# EEZ_DIB_DCP405_r2B7.net
KiCad netlist of a schematic drawn in EAGLE
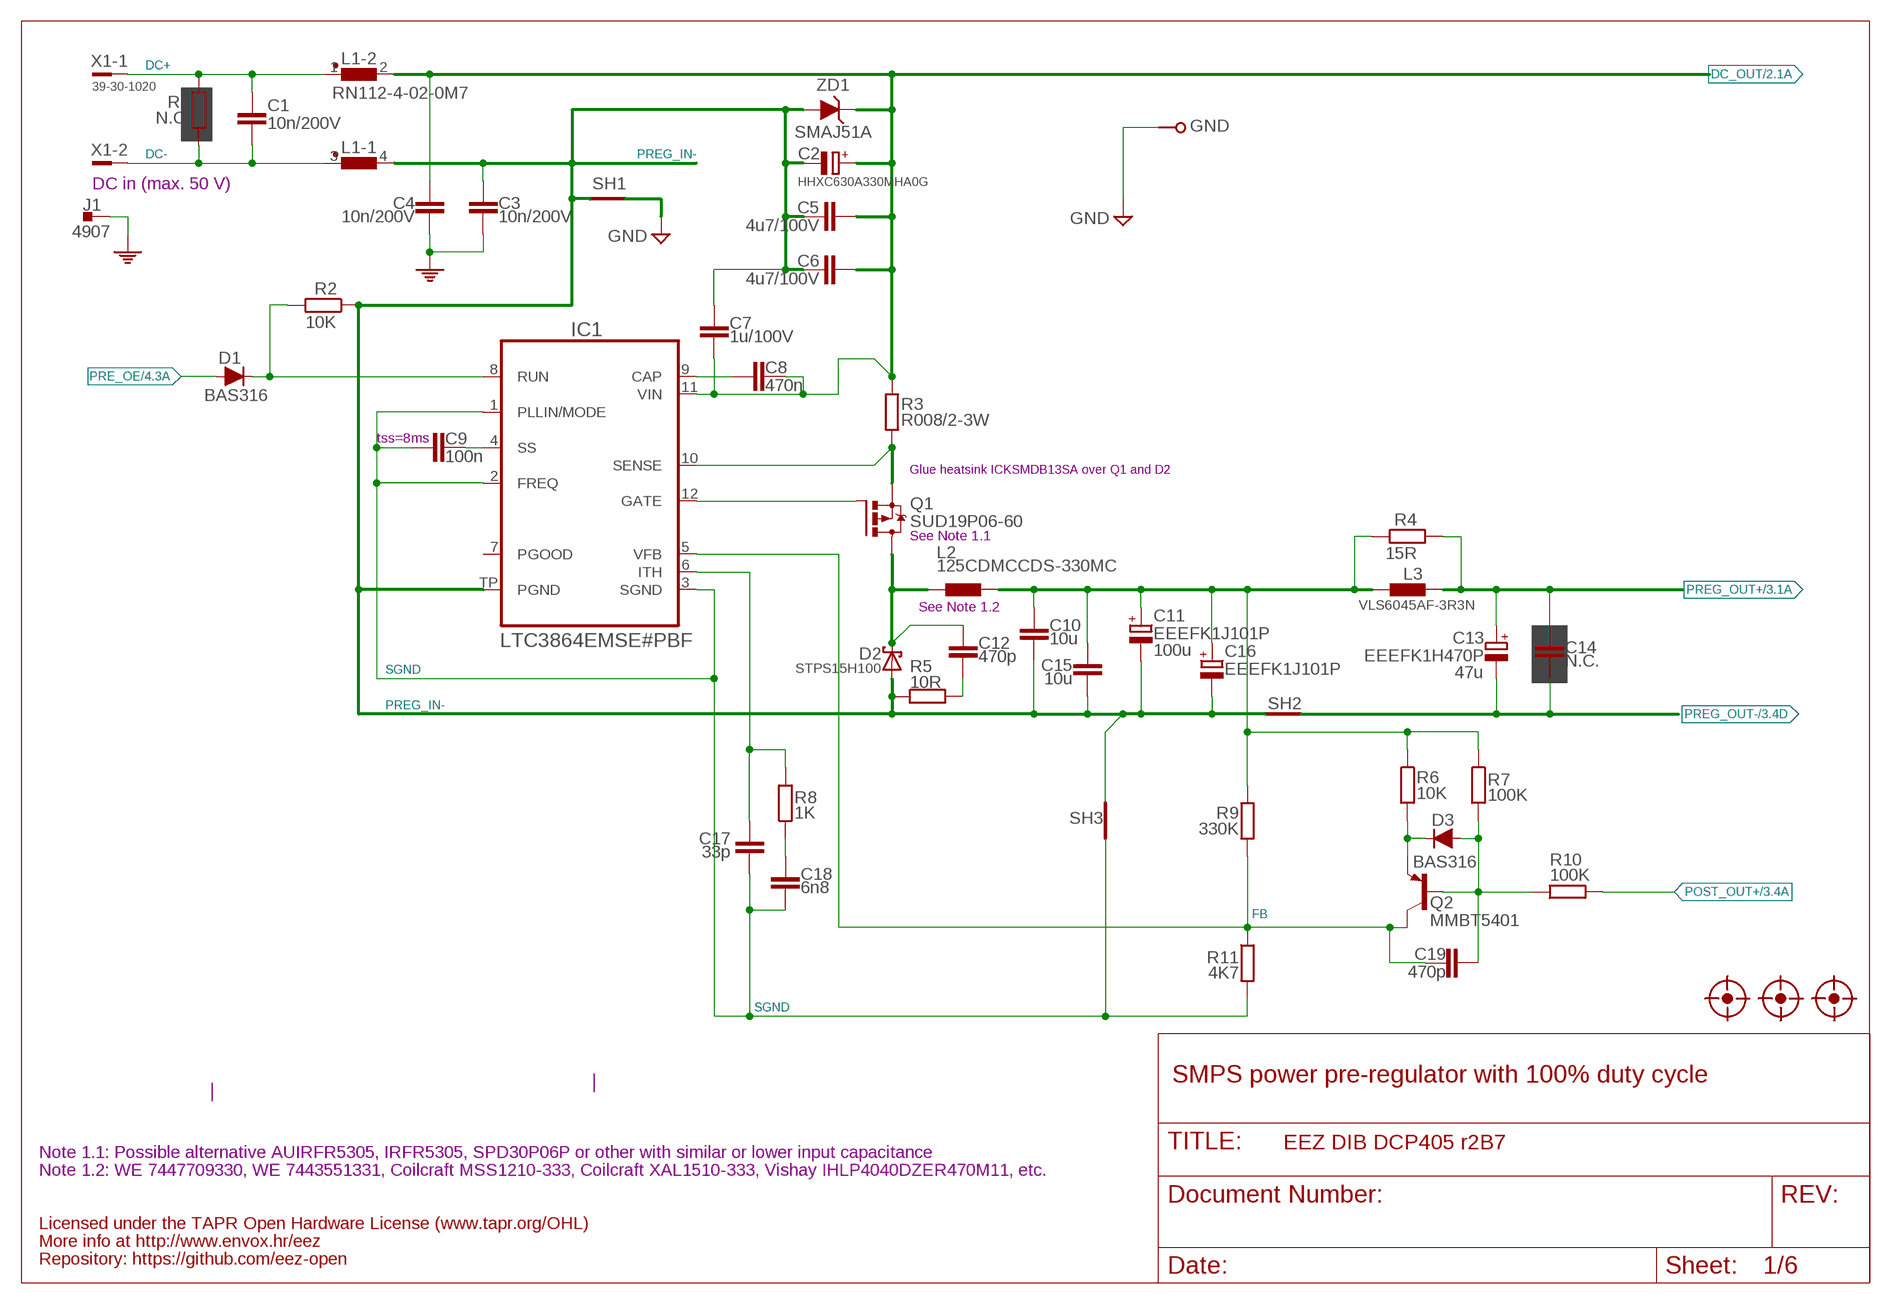
[diagram p0: schematic, sheet 1]
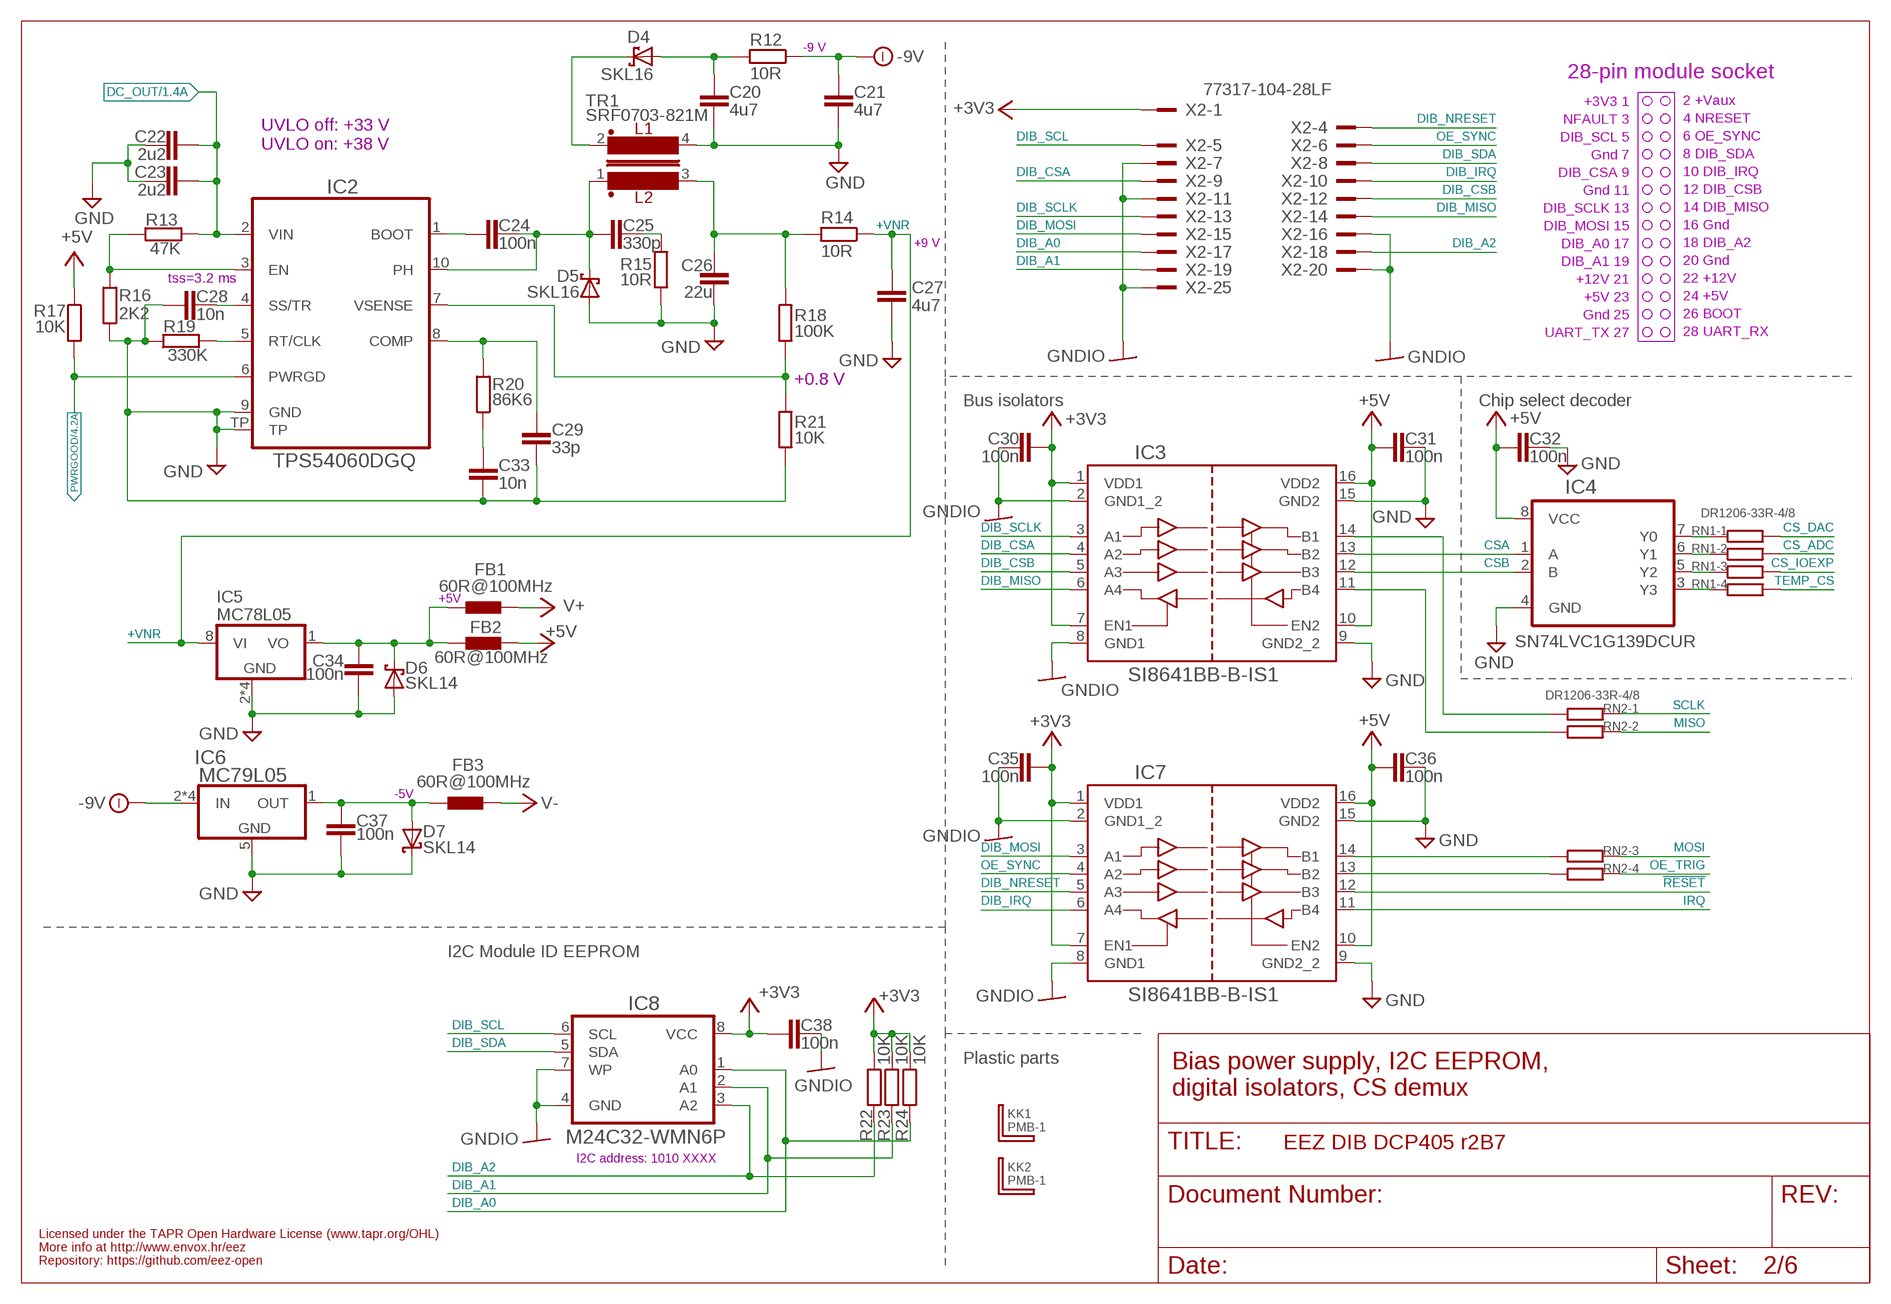
[diagram p1: schematic, sheet 2]
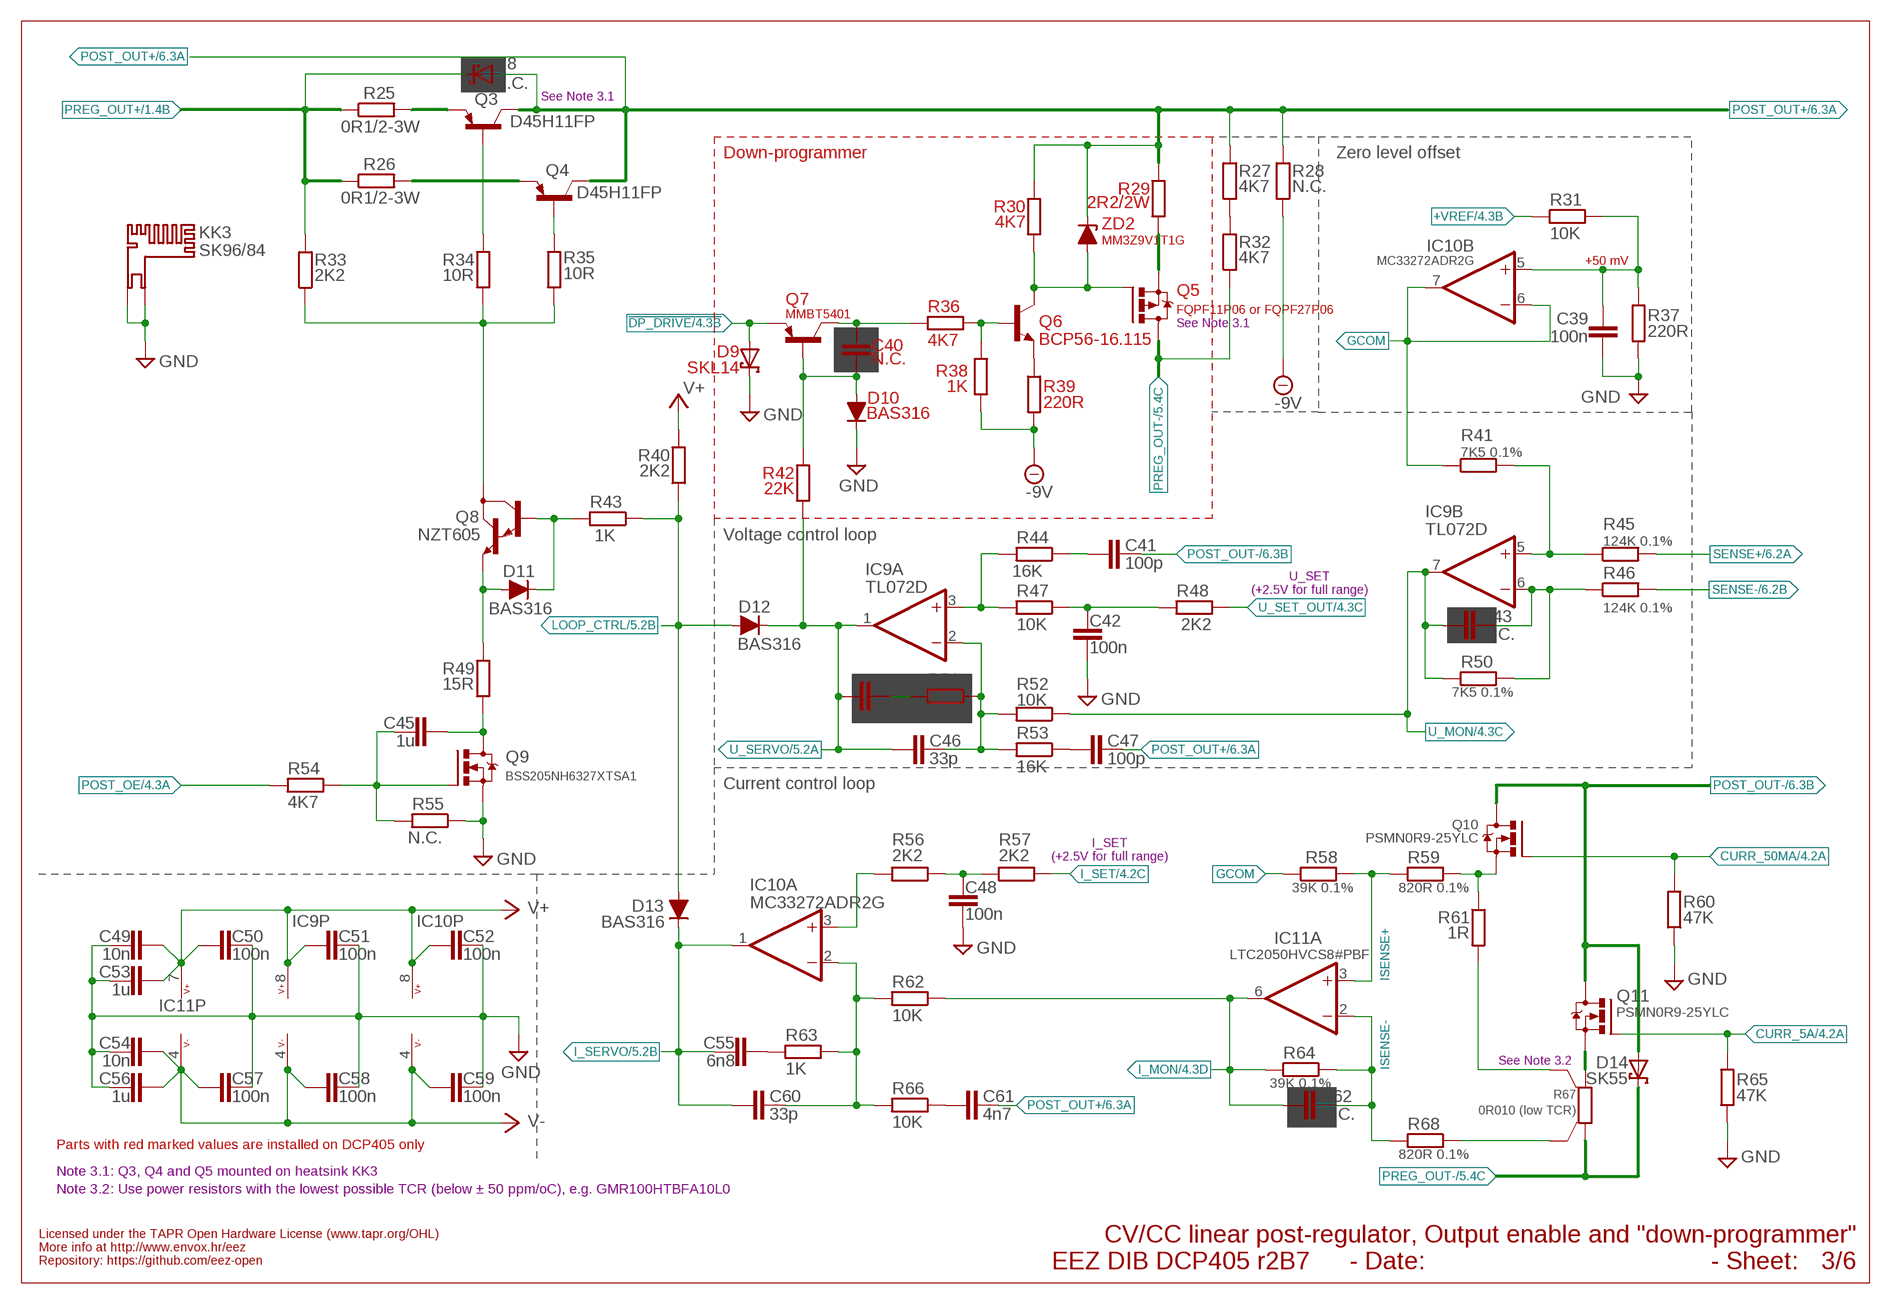
[diagram p2: schematic, sheet 3]
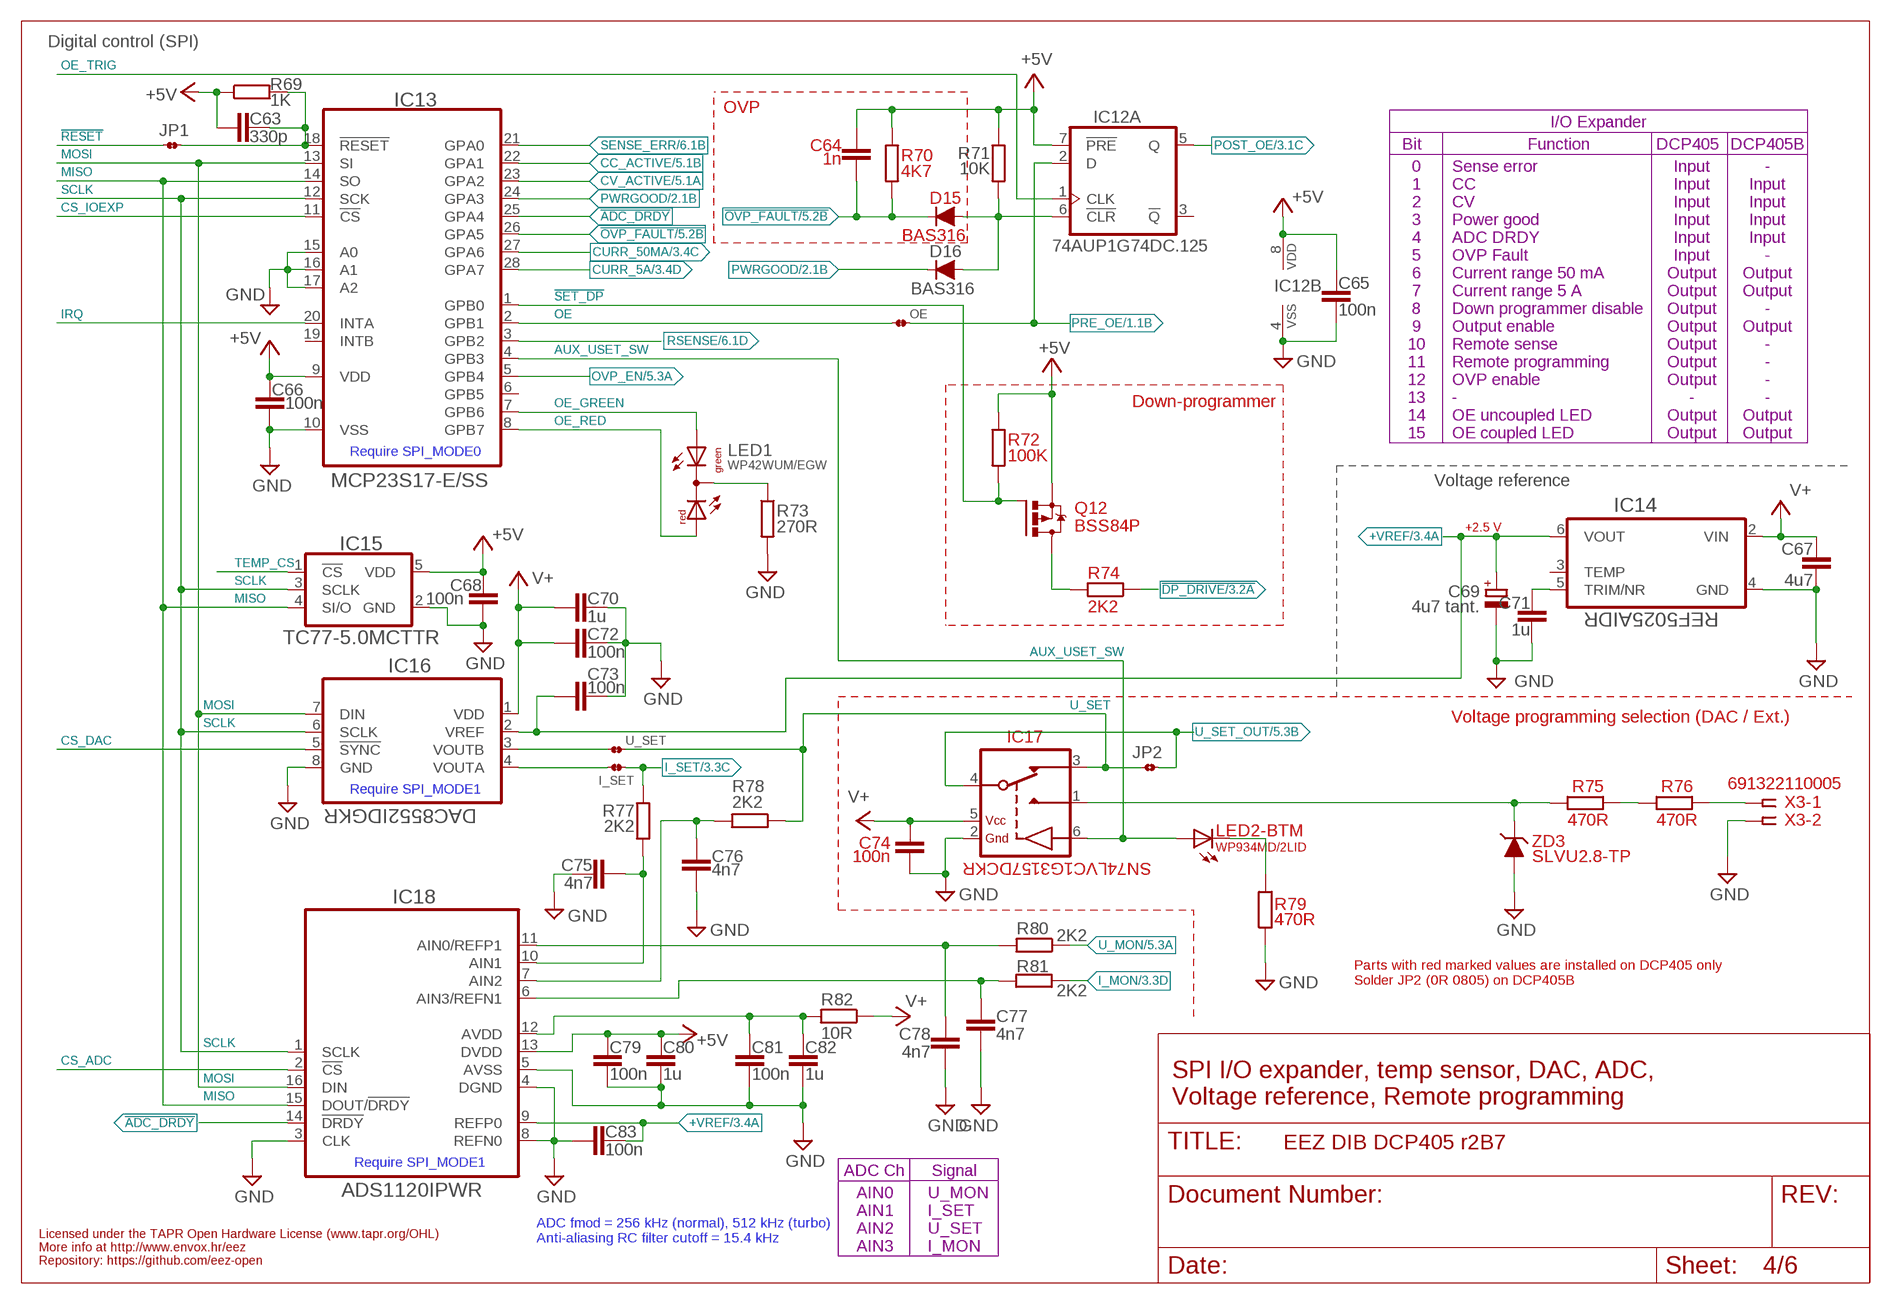
[diagram p3: schematic, sheet 4]
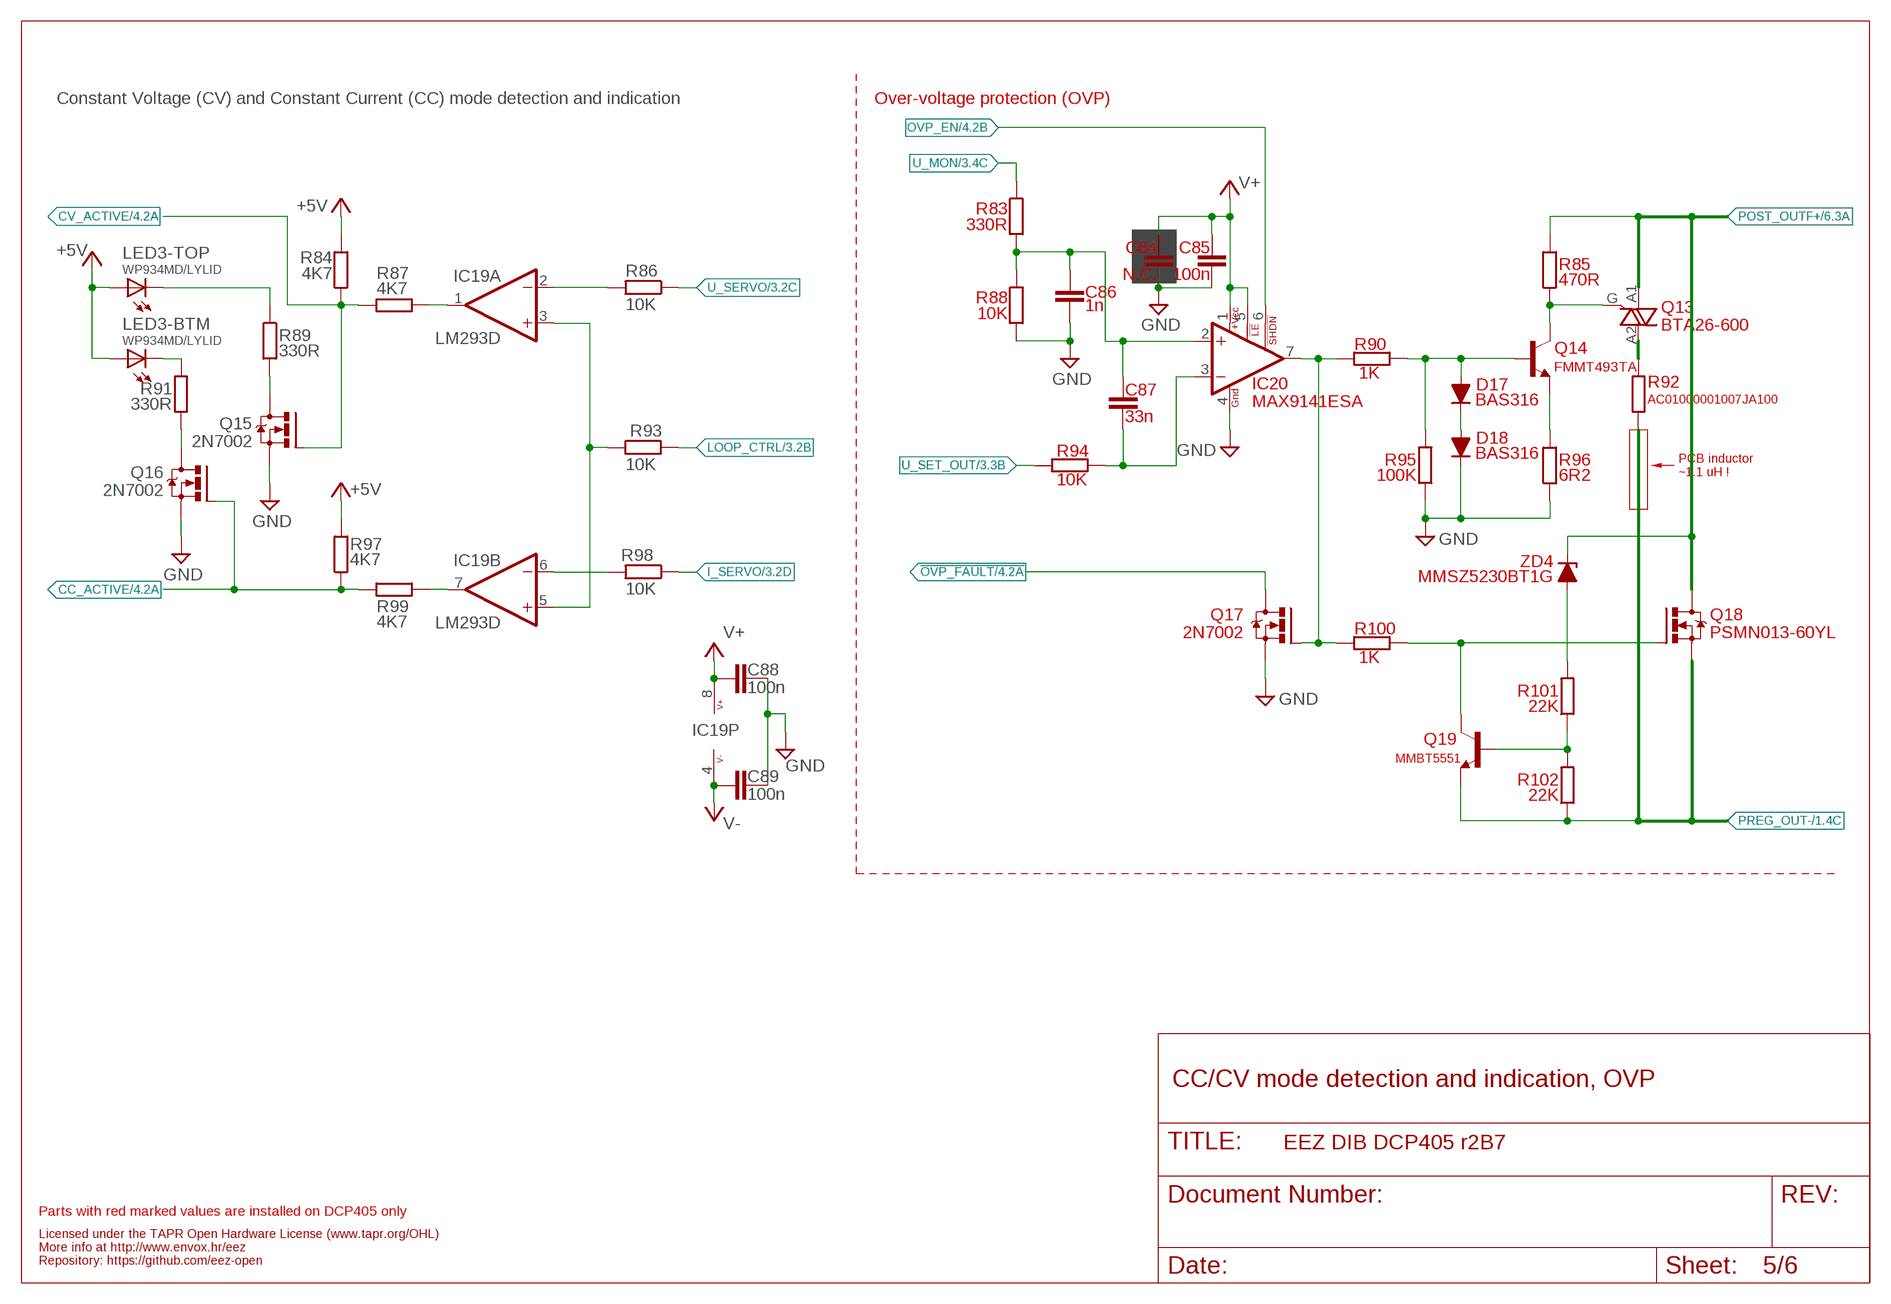
[diagram p4: schematic, sheet 5]
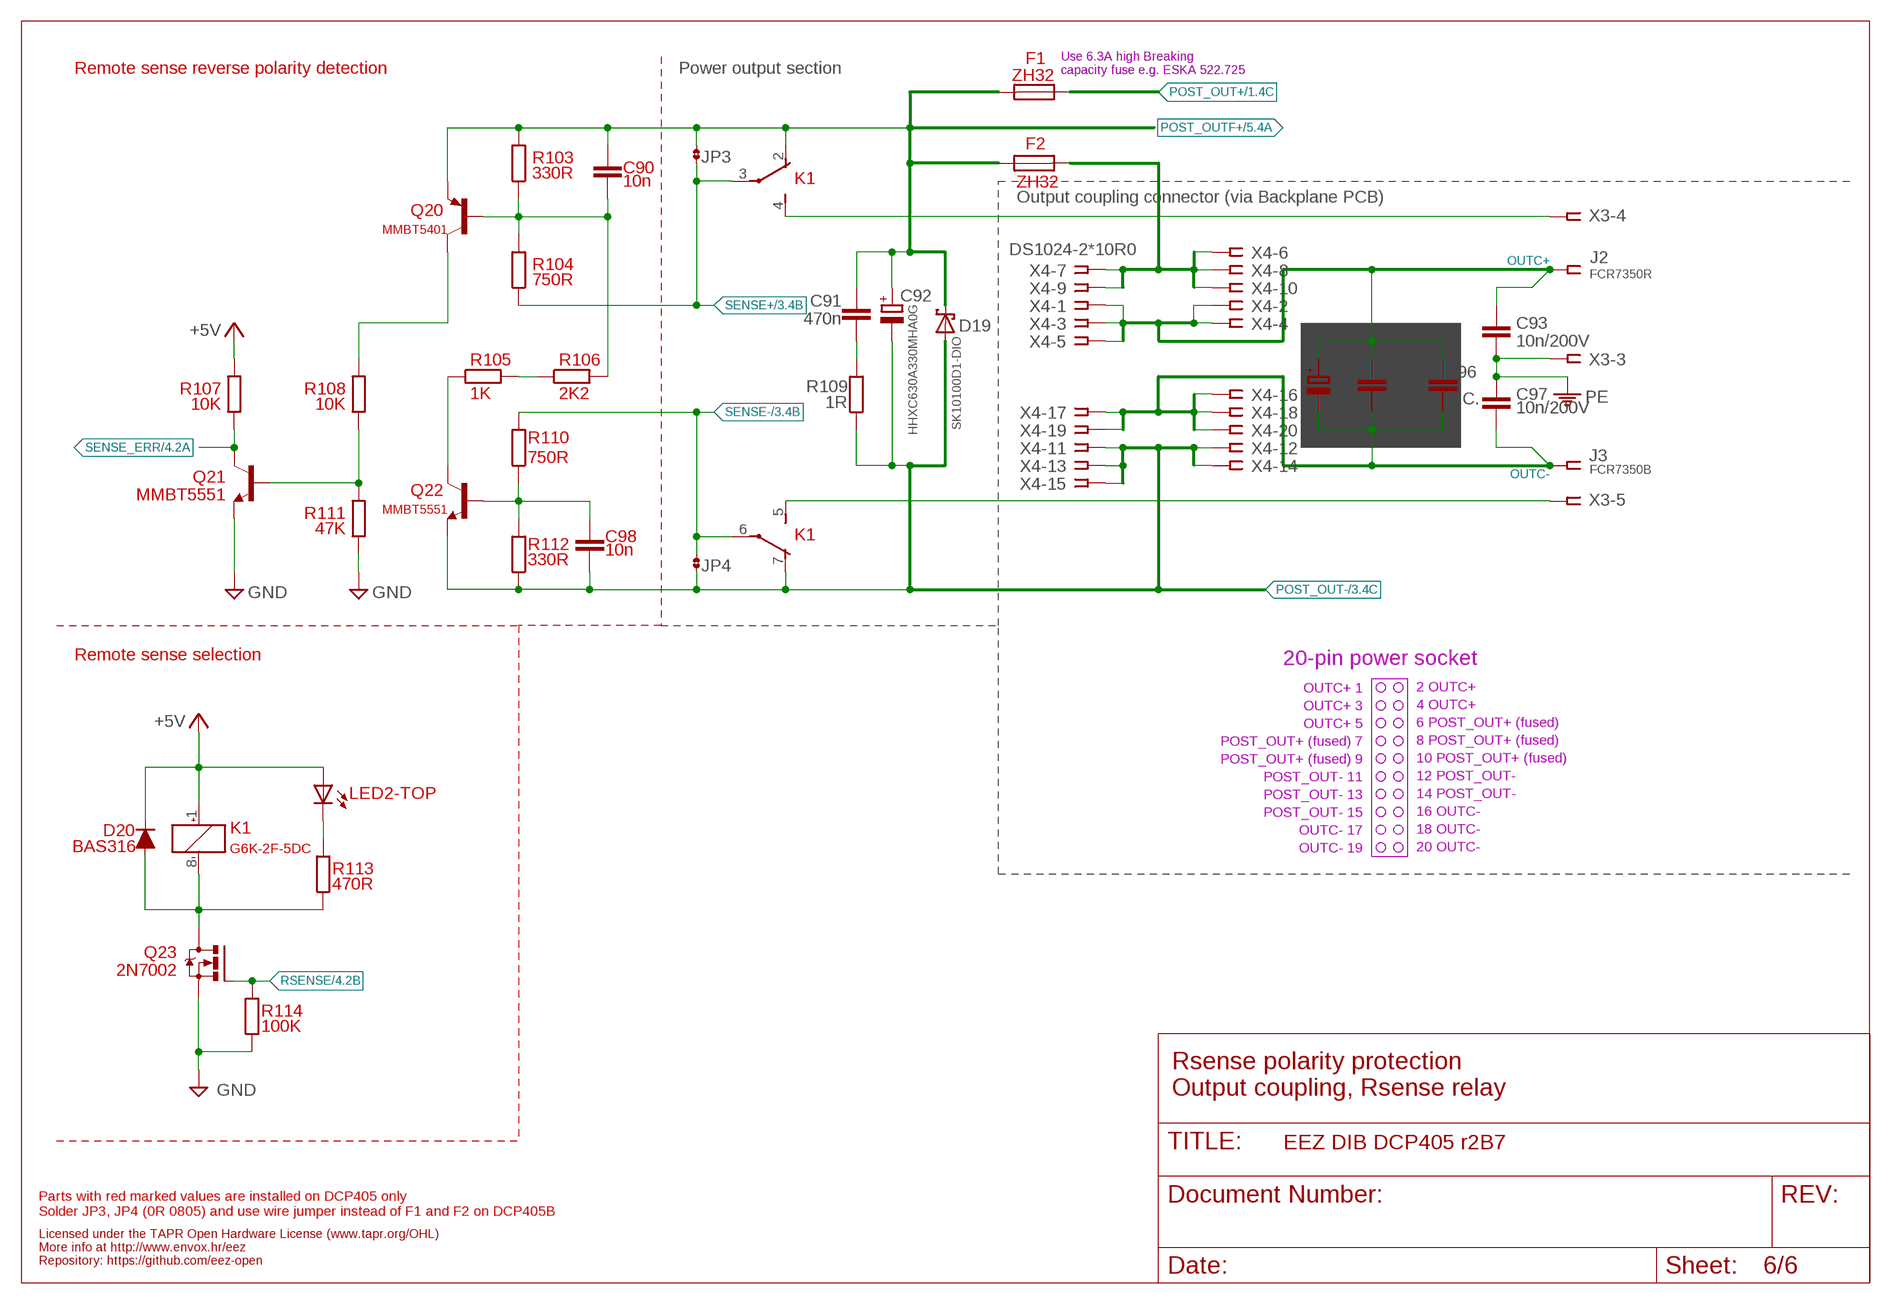
[diagram p5: schematic, sheet 6]

(export (version "E")
  (design (tool "Eeschema 10.0.6"))
  (components
    (comp (ref "C63")
      (value "330p")
      (footprint "eagle-import:C0805")
      (libsource (lib "eagle-import") (part "C-EUC0805"))
    )
    (comp (ref "C64")
      (value "1n")
      (footprint "eagle-import:C0805")
      (libsource (lib "eagle-import") (part "C-EUC0805"))
    )
    (comp (ref "C65")
      (value "100n")
      (footprint "eagle-import:C0603")
      (libsource (lib "eagle-import") (part "C-EUC0603"))
    )
    (comp (ref "C66")
      (value "100n")
      (footprint "eagle-import:C0603")
      (libsource (lib "eagle-import") (part "C-EUC0603"))
    )
    (comp (ref "C67")
      (value "4u7")
      (footprint "eagle-import:C1206")
      (libsource (lib "eagle-import") (part "C-EUC1206"))
    )
    (comp (ref "C68")
      (value "100n")
      (footprint "eagle-import:C0603")
      (libsource (lib "eagle-import") (part "C-EUC0603"))
    )
    (comp (ref "C69")
      (value "4u7 tant.")
      (footprint "eagle-import:EC1206")
      (libsource (lib "eagle-import") (part "ECAP1206"))
    )
    (comp (ref "C70")
      (value "1u")
      (footprint "eagle-import:C0805")
      (libsource (lib "eagle-import") (part "C-EUC0805"))
    )
    (comp (ref "C71")
      (value "1u")
      (footprint "eagle-import:C0805")
      (libsource (lib "eagle-import") (part "C-EUC0805"))
    )
    (comp (ref "C72")
      (value "100n")
      (footprint "eagle-import:C0603")
      (libsource (lib "eagle-import") (part "C-EUC0603"))
    )
    (comp (ref "C73")
      (value "100n")
      (footprint "eagle-import:C0603")
      (libsource (lib "eagle-import") (part "C-EUC0603"))
    )
    (comp (ref "C74")
      (value "100n")
      (footprint "eagle-import:C0603")
      (libsource (lib "eagle-import") (part "C-EUC0603"))
    )
    (comp (ref "C75")
      (value "4n7")
      (footprint "eagle-import:C0805")
      (libsource (lib "eagle-import") (part "C-EUC0805"))
    )
    (comp (ref "C76")
      (value "4n7")
      (footprint "eagle-import:C0805")
      (libsource (lib "eagle-import") (part "C-EUC0805"))
    )
    (comp (ref "C77")
      (value "4n7")
      (footprint "eagle-import:C0805")
      (libsource (lib "eagle-import") (part "C-EUC0805"))
    )
    (comp (ref "C78")
      (value "4n7")
      (footprint "eagle-import:C0805")
      (libsource (lib "eagle-import") (part "C-EUC0805"))
    )
    (comp (ref "C79")
      (value "100n")
      (footprint "eagle-import:C0603")
      (libsource (lib "eagle-import") (part "C-EUC0603"))
    )
    (comp (ref "C80")
      (value "1u")
      (footprint "eagle-import:C0805")
      (libsource (lib "eagle-import") (part "C-EUC0805"))
    )
    (comp (ref "C81")
      (value "100n")
      (footprint "eagle-import:C0603")
      (libsource (lib "eagle-import") (part "C-EUC0603"))
    )
    (comp (ref "C82")
      (value "1u")
      (footprint "eagle-import:C0805")
      (libsource (lib "eagle-import") (part "C-EUC0805"))
    )
    (comp (ref "C83")
      (value "100n")
      (footprint "eagle-import:C0603")
      (libsource (lib "eagle-import") (part "C-EUC0603"))
    )
    (comp (ref "D15")
      (value "BAS316")
      (footprint "eagle-import:SOD323-R")
      (libsource (lib "eagle-import") (part "DIODESOD323R"))
    )
    (comp (ref "D16")
      (value "BAS316")
      (footprint "eagle-import:SOD323-R")
      (libsource (lib "eagle-import") (part "DIODESOD323R"))
    )
    (comp (ref "IC12")
      (value "74AUP1G74DC.125")
      (footprint "eagle-import:DCU8")
      (libsource (lib "eagle-import") (part "SN74LVC1G74DCTR-VSSOP"))
    )
    (comp (ref "IC13")
      (value "MCP23S17-E/SS")
      (footprint "eagle-import:SOP65P780X200-28N")
      (libsource (lib "eagle-import") (part "MCP23S17-E/SSSSOP"))
    )
    (comp (ref "IC14")
      (value "REF5025AIDR")
      (footprint "eagle-import:SOIC127P600X175-8N")
      (libsource (lib "eagle-import") (part "REF50XX"))
    )
    (comp (ref "IC15")
      (value "TC77-5.0MCTTR")
      (footprint "eagle-import:SOT23-5")
      (libsource (lib "eagle-import") (part "TC77"))
    )
    (comp (ref "IC16")
      (value "DAC8552IDGKR")
      (footprint "eagle-import:DGK8-M")
      (libsource (lib "eagle-import") (part "DAC8552_DGK_8M"))
    )
    (comp (ref "IC17")
      (value "SN74LVC1G3157DCKR")
      (footprint "eagle-import:SOT65P210X110-6N")
      (libsource (lib "eagle-import") (part "SN74LVC1G3157-DCK"))
    )
    (comp (ref "IC18")
      (value "ADS1120IPWR")
      (footprint "eagle-import:PW(R-PDSO-G16)")
      (libsource (lib "eagle-import") (part "ADS1120TSSOP-16"))
    )
    (comp (ref "I_SET")
      (value "JP2-NOCUT")
      (footprint "eagle-import:JP2-NOCUT")
      (libsource (lib "eagle-import") (part "JP2-NOCUT"))
    )
    (comp (ref "JP1")
      (value "JP2-NOCUT")
      (footprint "eagle-import:JP2-NOCUT")
      (libsource (lib "eagle-import") (part "JP2-NOCUT"))
    )
    (comp (ref "JP2")
      (value "JP2-CUT-0805")
      (footprint "eagle-import:R_0805")
      (libsource (lib "eagle-import") (part "JP2-CUT-0805"))
    )
    (comp (ref "LED1")
      (value "WP42WUM/EGW")
      (footprint "eagle-import:L-42WUM-1EGWT")
      (libsource (lib "eagle-import") (part "LED_L-42WUM/1EGWT"))
    )
    (comp (ref "LED2")
      (value "WP934MD/2LID")
      (footprint "eagle-import:WP934MD")
      (libsource (lib "eagle-import") (part "WP934MD/2LID"))
    )
    (comp (ref "OE")
      (value "JP2-NOCUT")
      (footprint "eagle-import:JP2-NOCUT")
      (libsource (lib "eagle-import") (part "JP2-NOCUT"))
    )
    (comp (ref "Q12")
      (value "BSS84P")
      (footprint "eagle-import:SOT95P237X112-3N")
      (fields (field (name "MPN") "IRLML2246TRPBF"))
      (libsource (lib "eagle-import") (part "IRLML2246TRPBF"))
    )
    (comp (ref "R69")
      (value "1K")
      (footprint "eagle-import:R0805")
      (libsource (lib "eagle-import") (part "R-EU_R0805"))
    )
    (comp (ref "R70")
      (value "4K7")
      (footprint "eagle-import:R0805")
      (libsource (lib "eagle-import") (part "R-EU_R0805"))
    )
    (comp (ref "R71")
      (value "10K")
      (footprint "eagle-import:R0805")
      (libsource (lib "eagle-import") (part "R-EU_R0805"))
    )
    (comp (ref "R72")
      (value "100K")
      (footprint "eagle-import:R0805")
      (libsource (lib "eagle-import") (part "R-EU_R0805"))
    )
    (comp (ref "R73")
      (value "270R")
      (footprint "eagle-import:R0805")
      (libsource (lib "eagle-import") (part "R-EU_R0805"))
    )
    (comp (ref "R74")
      (value "2K2")
      (footprint "eagle-import:R0805")
      (libsource (lib "eagle-import") (part "R-EU_R0805"))
    )
    (comp (ref "R75")
      (value "470R")
      (footprint "eagle-import:R0805")
      (libsource (lib "eagle-import") (part "R-EU_R0805"))
    )
    (comp (ref "R76")
      (value "470R")
      (footprint "eagle-import:R0805")
      (libsource (lib "eagle-import") (part "R-EU_R0805"))
    )
    (comp (ref "R77")
      (value "2K2")
      (footprint "eagle-import:R0805")
      (libsource (lib "eagle-import") (part "R-EU_R0805"))
    )
    (comp (ref "R78")
      (value "2K2")
      (footprint "eagle-import:R0805")
      (libsource (lib "eagle-import") (part "R-EU_R0805"))
    )
    (comp (ref "R79")
      (value "470R")
      (footprint "eagle-import:R0805")
      (libsource (lib "eagle-import") (part "R-EU_R0805"))
    )
    (comp (ref "R80")
      (value "2K2")
      (footprint "eagle-import:R0805")
      (libsource (lib "eagle-import") (part "R-EU_R0805"))
    )
    (comp (ref "R81")
      (value "2K2")
      (footprint "eagle-import:R0805")
      (libsource (lib "eagle-import") (part "R-EU_R0805"))
    )
    (comp (ref "R82")
      (value "10R")
      (footprint "eagle-import:R1206")
      (libsource (lib "eagle-import") (part "R-EU_R1206"))
    )
    (comp (ref "U_SET")
      (value "JP2-NOCUT")
      (footprint "eagle-import:JP2-NOCUT")
      (libsource (lib "eagle-import") (part "JP2-NOCUT"))
    )
    (comp (ref "X3")
      (value "691322110005")
      (footprint "eagle-import:MC1,5_5-G-3,5")
      (libsource (lib "eagle-import") (part "MC1,5/5-G-3,5"))
    )
    (comp (ref "ZD3")
      (value "SLVU2.8-TP")
      (footprint "eagle-import:SOT23")
      (libsource (lib "eagle-import") (part "SLVU2.8"))
    )
    (comp (ref "C84")
      (value "N.C.")
      (footprint "eagle-import:C0805")
      (libsource (lib "eagle-import") (part "C-EUC0805"))
    )
    (comp (ref "C85")
      (value "100n")
      (footprint "eagle-import:C0603")
      (libsource (lib "eagle-import") (part "C-EUC0603"))
    )
    (comp (ref "C86")
      (value "1n")
      (footprint "eagle-import:C0805")
      (libsource (lib "eagle-import") (part "C-EUC0805"))
    )
    (comp (ref "C87")
      (value "33n")
      (footprint "eagle-import:C0805")
      (libsource (lib "eagle-import") (part "C-EUC0805"))
    )
    (comp (ref "C88")
      (value "100n")
      (footprint "eagle-import:C0603")
      (libsource (lib "eagle-import") (part "C-EUC0603"))
    )
    (comp (ref "C89")
      (value "100n")
      (footprint "eagle-import:C0603")
      (libsource (lib "eagle-import") (part "C-EUC0603"))
    )
    (comp (ref "D17")
      (value "BAS316")
      (footprint "eagle-import:SOD323-R")
      (libsource (lib "eagle-import") (part "DIODESOD323R"))
    )
    (comp (ref "D18")
      (value "BAS316")
      (footprint "eagle-import:SOD323-R")
      (libsource (lib "eagle-import") (part "DIODESOD323R"))
    )
    (comp (ref "IC19")
      (value "LM293D")
      (footprint "eagle-import:SOIC127P600X173-8N")
      (libsource (lib "eagle-import") (part "LM293D"))
    )
    (comp (ref "IC20")
      (value "MAX9141ESA")
      (footprint "eagle-import:SOIC127P600X173-8N")
      (libsource (lib "eagle-import") (part "MAX9141ESA"))
    )
    (comp (ref "LED3")
      (value "WP934MD/LYLID")
      (footprint "eagle-import:WP934MD")
      (libsource (lib "eagle-import") (part "WP934MD/LYLID"))
    )
    (comp (ref "Q13")
      (value "BTA26-600")
      (footprint "eagle-import:TOP3_TRIAC_NOHOLE")
      (libsource (lib "eagle-import") (part "BTA41-2"))
    )
    (comp (ref "Q14")
      (value "FMMT493TA")
      (footprint "eagle-import:SOT23-BEC")
      (libsource (lib "eagle-import") (part "-NPN-SOT23-BECMMBT5551LT1"))
    )
    (comp (ref "Q15")
      (value "2N7002")
      (footprint "eagle-import:SOT103P240X110-3N")
      (fields (field (name "MPN") "2N7002-7-F"))
      (libsource (lib "eagle-import") (part "2N7002"))
    )
    (comp (ref "Q16")
      (value "2N7002")
      (footprint "eagle-import:SOT103P240X110-3N")
      (fields (field (name "MPN") "2N7002-7-F"))
      (libsource (lib "eagle-import") (part "2N7002"))
    )
    (comp (ref "Q17")
      (value "2N7002")
      (footprint "eagle-import:SOT103P240X110-3N")
      (fields
        (field (name "MPN") "2N7002-7-F")
        (field (name "MPN_1") "2N7002-7-F")
        (field (name "OC_FARNELL") "1713823")
        (field (name "OC_NEWARK") "25R5679")
        (field (name "PACKAGE") "SOT-23-3")
        (field (name "SUPPLIER") "DIODES INC.")
      )
      (libsource (lib "eagle-import") (part "2N7002"))
    )
    (comp (ref "Q18")
      (value "PSMN013-60YL")
      (footprint "eagle-import:SOT669")
      (libsource (lib "eagle-import") (part "N-MOSFETLFPAK"))
    )
    (comp (ref "Q19")
      (value "MMBT5551")
      (footprint "eagle-import:SOT23-BEC")
      (libsource (lib "eagle-import") (part "-NPN-SOT23-BECMMBT5551LT1"))
    )
    (comp (ref "R83")
      (value "330R")
      (footprint "eagle-import:R0805")
      (libsource (lib "eagle-import") (part "R-EU_R0805"))
    )
    (comp (ref "R84")
      (value "4K7")
      (footprint "eagle-import:R0805")
      (libsource (lib "eagle-import") (part "R-EU_R0805"))
    )
    (comp (ref "R85")
      (value "470R")
      (footprint "eagle-import:R0805")
      (libsource (lib "eagle-import") (part "R-EU_R0805"))
    )
    (comp (ref "R86")
      (value "10K")
      (footprint "eagle-import:R0805")
      (libsource (lib "eagle-import") (part "R-EU_R0805"))
    )
    (comp (ref "R87")
      (value "4K7")
      (footprint "eagle-import:R0805")
      (libsource (lib "eagle-import") (part "R-EU_R0805"))
    )
    (comp (ref "R88")
      (value "10K")
      (footprint "eagle-import:R0805")
      (libsource (lib "eagle-import") (part "R-EU_R0805"))
    )
    (comp (ref "R89")
      (value "330R")
      (footprint "eagle-import:R0805")
      (libsource (lib "eagle-import") (part "R-EU_R0805"))
    )
    (comp (ref "R90")
      (value "1K")
      (footprint "eagle-import:R0805")
      (libsource (lib "eagle-import") (part "R-EU_R0805"))
    )
    (comp (ref "R91")
      (value "330R")
      (footprint "eagle-import:R0805")
      (libsource (lib "eagle-import") (part "R-EU_R0805"))
    )
    (comp (ref "R92")
      (value "AC01000001007JA100")
      (footprint "eagle-import:0411_15")
      (libsource (lib "eagle-import") (part "R-EU_0411/15"))
    )
    (comp (ref "R93")
      (value "10K")
      (footprint "eagle-import:R0805")
      (libsource (lib "eagle-import") (part "R-EU_R0805"))
    )
    (comp (ref "R94")
      (value "10K")
      (footprint "eagle-import:R0805")
      (libsource (lib "eagle-import") (part "R-EU_R0805"))
    )
    (comp (ref "R95")
      (value "100K")
      (footprint "eagle-import:R0805")
      (libsource (lib "eagle-import") (part "R-EU_R0805"))
    )
    (comp (ref "R96")
      (value "6R2")
      (footprint "eagle-import:R0805")
      (libsource (lib "eagle-import") (part "R-EU_R0805"))
    )
    (comp (ref "R97")
      (value "4K7")
      (footprint "eagle-import:R0805")
      (libsource (lib "eagle-import") (part "R-EU_R0805"))
    )
    (comp (ref "R98")
      (value "10K")
      (footprint "eagle-import:R0805")
      (libsource (lib "eagle-import") (part "R-EU_R0805"))
    )
    (comp (ref "R99")
      (value "4K7")
      (footprint "eagle-import:R0805")
      (libsource (lib "eagle-import") (part "R-EU_R0805"))
    )
    (comp (ref "R100")
      (value "1K")
      (footprint "eagle-import:R0805")
      (libsource (lib "eagle-import") (part "R-EU_R0805"))
    )
    (comp (ref "R101")
      (value "22K")
      (footprint "eagle-import:R0805")
      (libsource (lib "eagle-import") (part "R-EU_R0805"))
    )
    (comp (ref "R102")
      (value "22K")
      (footprint "eagle-import:R0805")
      (libsource (lib "eagle-import") (part "R-EU_R0805"))
    )
    (comp (ref "ZD4")
      (value "MMSZ5230BT1G")
      (footprint "eagle-import:SOD123")
      (libsource (lib "eagle-import") (part "ZENER-DIODESOD123"))
    )
    (comp (ref "C39")
      (value "100n")
      (footprint "eagle-import:C0603")
      (libsource (lib "eagle-import") (part "C-EUC0603"))
    )
    (comp (ref "C40")
      (value "N.C.")
      (footprint "eagle-import:C0805")
      (libsource (lib "eagle-import") (part "C-EUC0805"))
    )
    (comp (ref "C41")
      (value "100p")
      (footprint "eagle-import:C0805")
      (libsource (lib "eagle-import") (part "C-EUC0805"))
    )
    (comp (ref "C42")
      (value "100n")
      (footprint "eagle-import:C0603")
      (libsource (lib "eagle-import") (part "C-EUC0603"))
    )
    (comp (ref "C43")
      (value "N.C.")
      (footprint "eagle-import:C0805")
      (libsource (lib "eagle-import") (part "C-EUC0805"))
    )
    (comp (ref "C44")
      (value "N.C.")
      (footprint "eagle-import:C0805")
      (libsource (lib "eagle-import") (part "C-EUC0805"))
    )
    (comp (ref "C45")
      (value "1u")
      (footprint "eagle-import:C0805")
      (libsource (lib "eagle-import") (part "C-EUC0805"))
    )
    (comp (ref "C46")
      (value "33p")
      (footprint "eagle-import:C0805")
      (libsource (lib "eagle-import") (part "C-EUC0805"))
    )
    (comp (ref "C47")
      (value "100p")
      (footprint "eagle-import:C0805")
      (libsource (lib "eagle-import") (part "C-EUC0805"))
    )
    (comp (ref "C48")
      (value "100n")
      (footprint "eagle-import:C0603")
      (libsource (lib "eagle-import") (part "C-EUC0603"))
    )
    (comp (ref "C49")
      (value "10n")
      (footprint "eagle-import:C0805")
      (libsource (lib "eagle-import") (part "C-EUC0805"))
    )
    (comp (ref "C50")
      (value "100n")
      (footprint "eagle-import:C0603")
      (libsource (lib "eagle-import") (part "C-EUC0603"))
    )
    (comp (ref "C51")
      (value "100n")
      (footprint "eagle-import:C0603")
      (libsource (lib "eagle-import") (part "C-EUC0603"))
    )
    (comp (ref "C52")
      (value "100n")
      (footprint "eagle-import:C0603")
      (libsource (lib "eagle-import") (part "C-EUC0603"))
    )
    (comp (ref "C53")
      (value "1u")
      (footprint "eagle-import:C0805")
      (libsource (lib "eagle-import") (part "C-EUC0805"))
    )
    (comp (ref "C54")
      (value "10n")
      (footprint "eagle-import:C0805")
      (libsource (lib "eagle-import") (part "C-EUC0805"))
    )
    (comp (ref "C55")
      (value "6n8")
      (footprint "eagle-import:C0805")
      (libsource (lib "eagle-import") (part "C-EUC0805"))
    )
    (comp (ref "C56")
      (value "1u")
      (footprint "eagle-import:C0805")
      (libsource (lib "eagle-import") (part "C-EUC0805"))
    )
    (comp (ref "C57")
      (value "100n")
      (footprint "eagle-import:C0603")
      (libsource (lib "eagle-import") (part "C-EUC0603"))
    )
    (comp (ref "C58")
      (value "100n")
      (footprint "eagle-import:C0603")
      (libsource (lib "eagle-import") (part "C-EUC0603"))
    )
    (comp (ref "C59")
      (value "100n")
      (footprint "eagle-import:C0603")
      (libsource (lib "eagle-import") (part "C-EUC0603"))
    )
    (comp (ref "C60")
      (value "33p")
      (footprint "eagle-import:C0805")
      (libsource (lib "eagle-import") (part "C-EUC0805"))
    )
    (comp (ref "C61")
      (value "4n7")
      (footprint "eagle-import:C0805")
      (libsource (lib "eagle-import") (part "C-EUC0805"))
    )
    (comp (ref "C62")
      (value "N.C.")
      (footprint "eagle-import:C0805")
      (libsource (lib "eagle-import") (part "C-EUC0805"))
    )
    (comp (ref "D8")
      (value "N.C.")
      (footprint "eagle-import:SOD123")
      (libsource (lib "eagle-import") (part "SCHOTTKYSOD123"))
    )
    (comp (ref "D9")
      (value "SKL14")
      (footprint "eagle-import:SOD123")
      (libsource (lib "eagle-import") (part "SCHOTTKYSOD123"))
    )
    (comp (ref "D10")
      (value "BAS316")
      (footprint "eagle-import:SOD323-R")
      (libsource (lib "eagle-import") (part "DIODESOD323R"))
    )
    (comp (ref "D11")
      (value "BAS316")
      (footprint "eagle-import:SOD323-R")
      (libsource (lib "eagle-import") (part "DIODESOD323R"))
    )
    (comp (ref "D12")
      (value "BAS316")
      (footprint "eagle-import:SOD323-R")
      (libsource (lib "eagle-import") (part "DIODESOD323R"))
    )
    (comp (ref "D13")
      (value "BAS316")
      (footprint "eagle-import:SOD323-R")
      (libsource (lib "eagle-import") (part "DIODESOD323R"))
    )
    (comp (ref "D14")
      (value "SK55")
      (footprint "eagle-import:SMB")
      (libsource (lib "eagle-import") (part "SCHOTTKYSMB"))
    )
    (comp (ref "IC9")
      (value "TL072D")
      (footprint "eagle-import:SOIC127P600X173-8N")
      (libsource (lib "eagle-import") (part "TL072SOIC8"))
    )
    (comp (ref "IC10")
      (value "MC33272ADR2G")
      (footprint "eagle-import:SOIC127P600X173-8N")
      (libsource (lib "eagle-import") (part "TL072SOIC8"))
    )
    (comp (ref "IC11")
      (value "LTC2050HVCS8#PBF")
      (footprint "eagle-import:SOIC127P600X173-8N")
      (libsource (lib "eagle-import") (part "OP27GSZSO8"))
    )
    (comp (ref "KK3")
      (value "SK96/84")
      (footprint "eagle-import:SK96_84")
      (libsource (lib "eagle-import") (part "SK96/84"))
    )
    (comp (ref "Q3")
      (value "D45H11FP")
      (footprint "eagle-import:TO220FP-V")
      (libsource (lib "eagle-import") (part "D45H11-FPV"))
    )
    (comp (ref "Q4")
      (value "D45H11FP")
      (footprint "eagle-import:TO220FP-V")
      (libsource (lib "eagle-import") (part "D45H11-FPV"))
    )
    (comp (ref "Q5")
      (value "FQPF11P06 or FQPF27P06")
      (footprint "eagle-import:TO220FP-V")
      (libsource (lib "eagle-import") (part "P-MOSFET-FPV"))
    )
    (comp (ref "Q6")
      (value "BCP56-16.115")
      (footprint "eagle-import:SOT230P700X180-4N")
      (libsource (lib "eagle-import") (part "BCP56"))
    )
    (comp (ref "Q7")
      (value "MMBT5401")
      (footprint "eagle-import:SOT23-BEC")
      (libsource (lib "eagle-import") (part "-PNP-SOT23-BECBC857B"))
    )
    (comp (ref "Q8")
      (value "NZT605")
      (footprint "eagle-import:SOT230P700X180-4N")
      (libsource (lib "eagle-import") (part "NZT605"))
    )
    (comp (ref "Q9")
      (value "BSS205NH6327XTSA1")
      (footprint "eagle-import:SOT103P240X110-3N")
      (fields
        (field (name "MPN") "2N7002-7-F")
        (field (name "MPN_1") "2N7002-7-F")
        (field (name "OC_FARNELL") "1713823")
        (field (name "OC_NEWARK") "25R5679")
        (field (name "PACKAGE") "SOT-23-3")
        (field (name "SUPPLIER") "DIODES INC.")
      )
      (libsource (lib "eagle-import") (part "2N7002"))
    )
    (comp (ref "Q10")
      (value "PSMN0R9-25YLC")
      (footprint "eagle-import:SOT669")
      (libsource (lib "eagle-import") (part "N-MOSFETLFPAK"))
    )
    (comp (ref "Q11")
      (value "PSMN0R9-25YLC")
      (footprint "eagle-import:SOT669")
      (libsource (lib "eagle-import") (part "N-MOSFETLFPAK"))
    )
    (comp (ref "R25")
      (value "0R1/2-3W")
      (footprint "eagle-import:R2512")
      (libsource (lib "eagle-import") (part "R-EU_R2512"))
    )
    (comp (ref "R26")
      (value "0R1/2-3W")
      (footprint "eagle-import:R2512")
      (libsource (lib "eagle-import") (part "R-EU_R2512"))
    )
    (comp (ref "R27")
      (value "4K7")
      (footprint "eagle-import:R0805")
      (libsource (lib "eagle-import") (part "R-EU_R0805"))
    )
    (comp (ref "R28")
      (value "N.C.")
      (footprint "eagle-import:R0805")
      (libsource (lib "eagle-import") (part "R-EU_R0805"))
    )
    (comp (ref "R29")
      (value "2R2/2W")
      (footprint "eagle-import:R2512")
      (libsource (lib "eagle-import") (part "R-EU_R2512"))
    )
    (comp (ref "R30")
      (value "4K7")
      (footprint "eagle-import:R0805")
      (libsource (lib "eagle-import") (part "R-EU_R0805"))
    )
    (comp (ref "R31")
      (value "10K")
      (footprint "eagle-import:R0805")
      (libsource (lib "eagle-import") (part "R-EU_R0805"))
    )
    (comp (ref "R32")
      (value "4K7")
      (footprint "eagle-import:R0805")
      (libsource (lib "eagle-import") (part "R-EU_R0805"))
    )
    (comp (ref "R33")
      (value "2K2")
      (footprint "eagle-import:R0805")
      (libsource (lib "eagle-import") (part "R-EU_R0805"))
    )
    (comp (ref "R34")
      (value "10R")
      (footprint "eagle-import:R1206")
      (libsource (lib "eagle-import") (part "R-EU_R1206"))
    )
    (comp (ref "R35")
      (value "10R")
      (footprint "eagle-import:R1206")
      (libsource (lib "eagle-import") (part "R-EU_R1206"))
    )
    (comp (ref "R36")
      (value "4K7")
      (footprint "eagle-import:R0805")
      (libsource (lib "eagle-import") (part "R-EU_R0805"))
    )
    (comp (ref "R37")
      (value "220R")
      (footprint "eagle-import:R0805")
      (libsource (lib "eagle-import") (part "R-EU_R0805"))
    )
    (comp (ref "R38")
      (value "1K")
      (footprint "eagle-import:R0805")
      (libsource (lib "eagle-import") (part "R-EU_R0805"))
    )
    (comp (ref "R39")
      (value "220R")
      (footprint "eagle-import:R0805")
      (libsource (lib "eagle-import") (part "R-EU_R0805"))
    )
    (comp (ref "R40")
      (value "2K2")
      (footprint "eagle-import:R0805")
      (libsource (lib "eagle-import") (part "R-EU_R0805"))
    )
    (comp (ref "R41")
      (value "7K5 0.1%")
      (footprint "eagle-import:R0805")
      (libsource (lib "eagle-import") (part "R-EU_R0805"))
    )
    (comp (ref "R42")
      (value "22K")
      (footprint "eagle-import:R0805")
      (libsource (lib "eagle-import") (part "R-EU_R0805"))
    )
    (comp (ref "R43")
      (value "1K")
      (footprint "eagle-import:R0805")
      (libsource (lib "eagle-import") (part "R-EU_R0805"))
    )
    (comp (ref "R44")
      (value "16K")
      (footprint "eagle-import:R0805")
      (libsource (lib "eagle-import") (part "R-EU_R0805"))
    )
    (comp (ref "R45")
      (value "124K 0.1%")
      (footprint "eagle-import:R0805")
      (libsource (lib "eagle-import") (part "R-EU_R0805"))
    )
    (comp (ref "R46")
      (value "124K 0.1%")
      (footprint "eagle-import:R0805")
      (libsource (lib "eagle-import") (part "R-EU_R0805"))
    )
    (comp (ref "R47")
      (value "10K")
      (footprint "eagle-import:R0805")
      (libsource (lib "eagle-import") (part "R-EU_R0805"))
    )
    (comp (ref "R48")
      (value "2K2")
      (footprint "eagle-import:R0805")
      (libsource (lib "eagle-import") (part "R-EU_R0805"))
    )
    (comp (ref "R49")
      (value "15R")
      (footprint "eagle-import:R2010")
      (libsource (lib "eagle-import") (part "R-EU_R2010"))
    )
    (comp (ref "R50")
      (value "7K5 0.1%")
      (footprint "eagle-import:R0805")
      (libsource (lib "eagle-import") (part "R-EU_R0805"))
    )
    (comp (ref "R51")
      (value "N.C.")
      (footprint "eagle-import:R0805")
      (libsource (lib "eagle-import") (part "R-EU_R0805"))
    )
    (comp (ref "R52")
      (value "10K")
      (footprint "eagle-import:R0805")
      (libsource (lib "eagle-import") (part "R-EU_R0805"))
    )
    (comp (ref "R53")
      (value "16K")
      (footprint "eagle-import:R0805")
      (libsource (lib "eagle-import") (part "R-EU_R0805"))
    )
    (comp (ref "R54")
      (value "4K7")
      (footprint "eagle-import:R0805")
      (libsource (lib "eagle-import") (part "R-EU_R0805"))
    )
    (comp (ref "R55")
      (value "N.C.")
      (footprint "eagle-import:R0805")
      (libsource (lib "eagle-import") (part "R-EU_R0805"))
    )
    (comp (ref "R56")
      (value "2K2")
      (footprint "eagle-import:R0805")
      (libsource (lib "eagle-import") (part "R-EU_R0805"))
    )
    (comp (ref "R57")
      (value "2K2")
      (footprint "eagle-import:R0805")
      (libsource (lib "eagle-import") (part "R-EU_R0805"))
    )
    (comp (ref "R58")
      (value "39K 0.1%")
      (footprint "eagle-import:R0805")
      (libsource (lib "eagle-import") (part "R-EU_R0805"))
    )
    (comp (ref "R59")
      (value "820R 0.1%")
      (footprint "eagle-import:R0805")
      (libsource (lib "eagle-import") (part "R-EU_R0805"))
    )
    (comp (ref "R60")
      (value "47K")
      (footprint "eagle-import:R0805")
      (libsource (lib "eagle-import") (part "R-EU_R0805"))
    )
    (comp (ref "R61")
      (value "1R")
      (footprint "eagle-import:R1206")
      (libsource (lib "eagle-import") (part "R-EU_R1206"))
    )
    (comp (ref "R62")
      (value "10K")
      (footprint "eagle-import:R0805")
      (libsource (lib "eagle-import") (part "R-EU_R0805"))
    )
    (comp (ref "R63")
      (value "1K")
      (footprint "eagle-import:R0805")
      (libsource (lib "eagle-import") (part "R-EU_R0805"))
    )
    (comp (ref "R64")
      (value "39K 0.1%")
      (footprint "eagle-import:R0805")
      (libsource (lib "eagle-import") (part "R-EU_R0805"))
    )
    (comp (ref "R65")
      (value "47K")
      (footprint "eagle-import:R0805")
      (libsource (lib "eagle-import") (part "R-EU_R0805"))
    )
    (comp (ref "R66")
      (value "10K")
      (footprint "eagle-import:R0805")
      (libsource (lib "eagle-import") (part "R-EU_R0805"))
    )
    (comp (ref "R67")
      (value "0R010 (low TCR)")
      (footprint "eagle-import:R_2512-4WIRE")
      (libsource (lib "eagle-import") (part "R-EU_4WIRE2512"))
    )
    (comp (ref "R68")
      (value "820R 0.1%")
      (footprint "eagle-import:R0805")
      (libsource (lib "eagle-import") (part "R-EU_R0805"))
    )
    (comp (ref "ZD2")
      (value "MM3Z9V1T1G")
      (footprint "eagle-import:SOD323-R")
      (libsource (lib "eagle-import") (part "ZENER-DIODESOD323R"))
    )
    (comp (ref "C90")
      (value "10n")
      (footprint "eagle-import:C0805")
      (libsource (lib "eagle-import") (part "C-EUC0805"))
    )
    (comp (ref "C91")
      (value "470n")
      (footprint "eagle-import:C1206")
      (libsource (lib "eagle-import") (part "C-EUC1206"))
    )
    (comp (ref "C92")
      (value "HHXC630A330MHA0G")
      (footprint "eagle-import:CAPAE830X1050N")
      (libsource (lib "eagle-import") (part "ECAPSMD8.3MM/HA0"))
    )
    (comp (ref "C93")
      (value "10n/200V")
      (footprint "eagle-import:C1206")
      (libsource (lib "eagle-import") (part "C-EUC1206"))
    )
    (comp (ref "C94")
      (value "N.C.")
      (footprint "eagle-import:ECAP2_5")
      (libsource (lib "eagle-import") (part "ECAP2G/5"))
    )
    (comp (ref "C95")
      (value "N.C.")
      (footprint "eagle-import:C0805")
      (libsource (lib "eagle-import") (part "C-EUC0805"))
    )
    (comp (ref "C96")
      (value "N.C.")
      (footprint "eagle-import:C0805")
      (libsource (lib "eagle-import") (part "C-EUC0805"))
    )
    (comp (ref "C97")
      (value "10n/200V")
      (footprint "eagle-import:C1206")
      (libsource (lib "eagle-import") (part "C-EUC1206"))
    )
    (comp (ref "C98")
      (value "10n")
      (footprint "eagle-import:C0805")
      (libsource (lib "eagle-import") (part "C-EUC0805"))
    )
    (comp (ref "D19")
      (value "SK10100D1-DIO")
      (footprint "eagle-import:TO252-L")
      (libsource (lib "eagle-import") (part "SCHOTTKY-DUAL_A_L"))
    )
    (comp (ref "D20")
      (value "BAS316")
      (footprint "eagle-import:SOD323-R")
      (libsource (lib "eagle-import") (part "DIODESOD323R"))
    )
    (comp (ref "F1")
      (value "ZH32")
      (footprint "eagle-import:ZH32")
      (libsource (lib "eagle-import") (part "ZH32"))
    )
    (comp (ref "F2")
      (value "ZH32")
      (footprint "eagle-import:ZH32")
      (libsource (lib "eagle-import") (part "ZH32"))
    )
    (comp (ref "J2")
      (value "FCR7350R")
      (footprint "eagle-import:S16N-PC")
      (libsource (lib "eagle-import") (part "BINDING_POSTCLIFF"))
    )
    (comp (ref "J3")
      (value "FCR7350B")
      (footprint "eagle-import:S16N-PC")
      (libsource (lib "eagle-import") (part "BINDING_POSTCLIFF"))
    )
    (comp (ref "JP3")
      (value "JP2-CUT-0805")
      (footprint "eagle-import:R_0805")
      (libsource (lib "eagle-import") (part "JP2-CUT-0805"))
    )
    (comp (ref "JP4")
      (value "JP2-CUT-0805")
      (footprint "eagle-import:R_0805")
      (libsource (lib "eagle-import") (part "JP2-CUT-0805"))
    )
    (comp (ref "K1")
      (value "G6K-2F-5DC")
      (footprint "eagle-import:G6K-2F")
      (fields
        (field (name "MF") "OMRON COMPONENTS USA")
        (field (name "MPN") "G6K-2F DC24")
        (field (name "MF_1") "OMRON COMPONENTS USA")
        (field (name "MPN_1") "G6K-2F DC24")
        (field (name "OC_FARNELL") "1690427")
        (field (name "OC_NEWARK") "36K7467")
      )
      (libsource (lib "eagle-import") (part "G6K-2F"))
    )
    (comp (ref "Q20")
      (value "MMBT5401")
      (footprint "eagle-import:SOT23-BEC")
      (libsource (lib "eagle-import") (part "-PNP-SOT23-BECBC857B"))
    )
    (comp (ref "Q21")
      (value "MMBT5551")
      (footprint "eagle-import:SOT23-BEC")
      (libsource (lib "eagle-import") (part "-NPN-SOT23-BECMMBT5551LT1"))
    )
    (comp (ref "Q22")
      (value "MMBT5551")
      (footprint "eagle-import:SOT23-BEC")
      (libsource (lib "eagle-import") (part "-NPN-SOT23-BECMMBT5551LT1"))
    )
    (comp (ref "Q23")
      (value "2N7002")
      (footprint "eagle-import:SOT103P240X110-3N")
      (fields
        (field (name "MPN") "2N7002-7-F")
        (field (name "MPN_1") "2N7002-7-F")
        (field (name "OC_FARNELL") "1713823")
        (field (name "OC_NEWARK") "25R5679")
        (field (name "PACKAGE") "SOT-23-3")
        (field (name "SUPPLIER") "DIODES INC.")
      )
      (libsource (lib "eagle-import") (part "2N7002"))
    )
    (comp (ref "R103")
      (value "330R")
      (footprint "eagle-import:R0805")
      (libsource (lib "eagle-import") (part "R-EU_R0805"))
    )
    (comp (ref "R104")
      (value "750R")
      (footprint "eagle-import:R0805")
      (libsource (lib "eagle-import") (part "R-EU_R0805"))
    )
    (comp (ref "R105")
      (value "1K")
      (footprint "eagle-import:R0805")
      (libsource (lib "eagle-import") (part "R-EU_R0805"))
    )
    (comp (ref "R106")
      (value "2K2")
      (footprint "eagle-import:R0805")
      (libsource (lib "eagle-import") (part "R-EU_R0805"))
    )
    (comp (ref "R107")
      (value "10K")
      (footprint "eagle-import:R0805")
      (libsource (lib "eagle-import") (part "R-EU_R0805"))
    )
    (comp (ref "R108")
      (value "10K")
      (footprint "eagle-import:R0805")
      (libsource (lib "eagle-import") (part "R-EU_R0805"))
    )
    (comp (ref "R109")
      (value "1R")
      (footprint "eagle-import:R0805")
      (libsource (lib "eagle-import") (part "R-EU_R0805"))
    )
    (comp (ref "R110")
      (value "750R")
      (footprint "eagle-import:R0805")
      (libsource (lib "eagle-import") (part "R-EU_R0805"))
    )
    (comp (ref "R111")
      (value "47K")
      (footprint "eagle-import:R0805")
      (libsource (lib "eagle-import") (part "R-EU_R0805"))
    )
    (comp (ref "R112")
      (value "330R")
      (footprint "eagle-import:R0805")
      (libsource (lib "eagle-import") (part "R-EU_R0805"))
    )
    (comp (ref "R113")
      (value "470R")
      (footprint "eagle-import:R0805")
      (libsource (lib "eagle-import") (part "R-EU_R0805"))
    )
    (comp (ref "R114")
      (value "100K")
      (footprint "eagle-import:R0805")
      (libsource (lib "eagle-import") (part "R-EU_R0805"))
    )
    (comp (ref "X4")
      (value "DS1024-2*10R0")
      (footprint "eagle-import:SSW-110-02-T-D-RA")
      (libsource (lib "eagle-import") (part "SSW-110-02-T-D-RA"))
    )
    (comp (ref "C1")
      (value "10n/200V")
      (footprint "eagle-import:C1206")
      (libsource (lib "eagle-import") (part "C-EUC1206"))
    )
    (comp (ref "C2")
      (value "HHXC630A330MHA0G")
      (footprint "eagle-import:CAPAE830X1050N")
      (libsource (lib "eagle-import") (part "ECAPSMD8.3MM/HA0"))
    )
    (comp (ref "C3")
      (value "10n/200V")
      (footprint "eagle-import:C1206")
      (libsource (lib "eagle-import") (part "C-EUC1206"))
    )
    (comp (ref "C4")
      (value "10n/200V")
      (footprint "eagle-import:C1206")
      (libsource (lib "eagle-import") (part "C-EUC1206"))
    )
    (comp (ref "C5")
      (value "4u7/100V")
      (footprint "eagle-import:C1210")
      (libsource (lib "eagle-import") (part "C-EUC1210"))
    )
    (comp (ref "C6")
      (value "4u7/100V")
      (footprint "eagle-import:C1210")
      (libsource (lib "eagle-import") (part "C-EUC1210"))
    )
    (comp (ref "C7")
      (value "1u/100V")
      (footprint "eagle-import:C1206")
      (libsource (lib "eagle-import") (part "C-EUC1206"))
    )
    (comp (ref "C8")
      (value "470n")
      (footprint "eagle-import:C0805")
      (libsource (lib "eagle-import") (part "C-EUC0805"))
    )
    (comp (ref "C9")
      (value "100n")
      (footprint "eagle-import:C0603")
      (libsource (lib "eagle-import") (part "C-EUC0603"))
    )
    (comp (ref "C10")
      (value "10u")
      (footprint "eagle-import:C1210")
      (libsource (lib "eagle-import") (part "C-EUC1210"))
    )
    (comp (ref "C11")
      (value "EEEFK1J101P")
      (footprint "eagle-import:CAPAE1030X1050N")
      (libsource (lib "eagle-import") (part "ECAP10X10"))
    )
    (comp (ref "C12")
      (value "470p")
      (footprint "eagle-import:C0805")
      (libsource (lib "eagle-import") (part "C-EUC0805"))
    )
    (comp (ref "C13")
      (value "EEEFK1H470P")
      (footprint "eagle-import:CAPAE830X1050N")
      (libsource (lib "eagle-import") (part "ECAPSMD8.3MM/HA0"))
    )
    (comp (ref "C14")
      (value "N.C.")
      (footprint "eagle-import:C0805")
      (libsource (lib "eagle-import") (part "C-EUC0805"))
    )
    (comp (ref "C15")
      (value "10u")
      (footprint "eagle-import:C1210")
      (libsource (lib "eagle-import") (part "C-EUC1210"))
    )
    (comp (ref "C16")
      (value "EEEFK1J101P")
      (footprint "eagle-import:CAPAE1030X1050N")
      (libsource (lib "eagle-import") (part "ECAP10X10"))
    )
    (comp (ref "C17")
      (value "33p")
      (footprint "eagle-import:C0805")
      (libsource (lib "eagle-import") (part "C-EUC0805"))
    )
    (comp (ref "C18")
      (value "6n8")
      (footprint "eagle-import:C0805")
      (libsource (lib "eagle-import") (part "C-EUC0805"))
    )
    (comp (ref "C19")
      (value "470p")
      (footprint "eagle-import:C0805")
      (libsource (lib "eagle-import") (part "C-EUC0805"))
    )
    (comp (ref "D1")
      (value "BAS316")
      (footprint "eagle-import:SOD323-R")
      (libsource (lib "eagle-import") (part "DIODESOD323R"))
    )
    (comp (ref "D2")
      (value "STPS15H100")
      (footprint "eagle-import:TO252-L")
      (libsource (lib "eagle-import") (part "SCHOTTKY-DUAL_A_L"))
    )
    (comp (ref "D3")
      (value "BAS316")
      (footprint "eagle-import:SOD323-R")
      (libsource (lib "eagle-import") (part "DIODESOD323R"))
    )
    (comp (ref "FM1")
      (value "FIDUCIAL_2")
      (footprint "eagle-import:FIDUCIAL_DUAL")
      (libsource (lib "eagle-import") (part "FIDUCIAL_2"))
    )
    (comp (ref "FM2")
      (value "FIDUCIAL_2")
      (footprint "eagle-import:FIDUCIAL_DUAL")
      (libsource (lib "eagle-import") (part "FIDUCIAL_2"))
    )
    (comp (ref "FM3")
      (value "FIDUCIAL_2")
      (footprint "eagle-import:FIDUCIAL_DUAL")
      (libsource (lib "eagle-import") (part "FIDUCIAL_2"))
    )
    (comp (ref "GND")
      (value "PCB_TEST_TABSHIELD")
      (footprint "eagle-import:PCB_SHIELD_TAB")
      (libsource (lib "eagle-import") (part "PCB_TEST_TABSHIELD"))
    )
    (comp (ref "IC1")
      (value "LTC3864EMSE#PBF")
      (footprint "eagle-import:LTC_05-08-1666")
      (libsource (lib "eagle-import") (part "LTC3864"))
    )
    (comp (ref "J1")
      (value "4907")
      (footprint "eagle-import:PCB_TAB-4907")
      (libsource (lib "eagle-import") (part "PCB_TAB-4907"))
    )
    (comp (ref "L1")
      (value "RN112-4-02-0M7")
      (footprint "eagle-import:RN112")
      (libsource (lib "eagle-import") (part "RN112"))
    )
    (comp (ref "L2")
      (value "125CDMCCDS-330MC")
      (footprint "eagle-import:125CDMCC_DS")
      (libsource (lib "eagle-import") (part "125CDMCC/DS"))
    )
    (comp (ref "L3")
      (value "VLS6045AF-3R3N")
      (footprint "eagle-import:COILCRAFT_HPI0630")
      (libsource (lib "eagle-import") (part "COILCRAFT_HPI0630"))
    )
    (comp (ref "Q1")
      (value "SUD19P06-60")
      (footprint "eagle-import:TO229P990X239-3N")
      (libsource (lib "eagle-import") (part "P-MOSFETDPAK"))
    )
    (comp (ref "Q2")
      (value "MMBT5401")
      (footprint "eagle-import:SOT23-BEC")
      (libsource (lib "eagle-import") (part "-PNP-SOT23-BECBC857B"))
    )
    (comp (ref "R1")
      (value "N.C.")
      (footprint "eagle-import:R2512")
      (libsource (lib "eagle-import") (part "R-EU_R2512"))
    )
    (comp (ref "R2")
      (value "10K")
      (footprint "eagle-import:R0805")
      (libsource (lib "eagle-import") (part "R-EU_R0805"))
    )
    (comp (ref "R3")
      (value "R008/2-3W")
      (footprint "eagle-import:R2512")
      (libsource (lib "eagle-import") (part "R-EU_R2512"))
    )
    (comp (ref "R4")
      (value "15R")
      (footprint "eagle-import:R2010")
      (libsource (lib "eagle-import") (part "R-EU_R2010"))
    )
    (comp (ref "R5")
      (value "10R")
      (footprint "eagle-import:R1206")
      (libsource (lib "eagle-import") (part "R-EU_R1206"))
    )
    (comp (ref "R6")
      (value "10K")
      (footprint "eagle-import:R0805")
      (libsource (lib "eagle-import") (part "R-EU_R0805"))
    )
    (comp (ref "R7")
      (value "100K")
      (footprint "eagle-import:R0805")
      (libsource (lib "eagle-import") (part "R-EU_R0805"))
    )
    (comp (ref "R8")
      (value "1K")
      (footprint "eagle-import:R0805")
      (libsource (lib "eagle-import") (part "R-EU_R0805"))
    )
    (comp (ref "R9")
      (value "330K")
      (footprint "eagle-import:R0805")
      (libsource (lib "eagle-import") (part "R-EU_R0805"))
    )
    (comp (ref "R10")
      (value "100K")
      (footprint "eagle-import:R0805")
      (libsource (lib "eagle-import") (part "R-EU_R0805"))
    )
    (comp (ref "R11")
      (value "4K7")
      (footprint "eagle-import:R0805")
      (libsource (lib "eagle-import") (part "R-EU_R0805"))
    )
    (comp (ref "SH1")
      (value "SHORTNOHOLE")
      (footprint "eagle-import:SHORT_NOHOLE")
      (libsource (lib "eagle-import") (part "SHORTNOHOLE"))
    )
    (comp (ref "SH2")
      (value "Pgnd to Pout- short")
      (footprint "eagle-import:SHORT_NOHOLE")
      (libsource (lib "eagle-import") (part "SHORTNOHOLE"))
    )
    (comp (ref "SH3")
      (value "Sgnd to Pgnd short")
      (footprint "eagle-import:SHORT_NOHOLE")
      (libsource (lib "eagle-import") (part "SHORTNOHOLE"))
    )
    (comp (ref "X1")
      (value "39-30-1020")
      (footprint "eagle-import:MINIFIT_39301020")
      (libsource (lib "eagle-import") (part "MINIFIT_39301020"))
    )
    (comp (ref "ZD1")
      (value "SMAJ51A")
      (footprint "eagle-import:DO214AA")
      (libsource (lib "eagle-import") (part "P6SMB68A"))
    )
    (comp (ref "C20")
      (value "4u7")
      (footprint "eagle-import:C1206")
      (libsource (lib "eagle-import") (part "C-EUC1206"))
    )
    (comp (ref "C21")
      (value "4u7")
      (footprint "eagle-import:C1206")
      (libsource (lib "eagle-import") (part "C-EUC1206"))
    )
    (comp (ref "C22")
      (value "2u2")
      (footprint "eagle-import:C1206")
      (libsource (lib "eagle-import") (part "C-EUC1206"))
    )
    (comp (ref "C23")
      (value "2u2")
      (footprint "eagle-import:C1206")
      (libsource (lib "eagle-import") (part "C-EUC1206"))
    )
    (comp (ref "C24")
      (value "100n")
      (footprint "eagle-import:C0603")
      (libsource (lib "eagle-import") (part "C-EUC0603"))
    )
    (comp (ref "C25")
      (value "330p")
      (footprint "eagle-import:C0805")
      (libsource (lib "eagle-import") (part "C-EUC0805"))
    )
    (comp (ref "C26")
      (value "22u")
      (footprint "eagle-import:C1210")
      (libsource (lib "eagle-import") (part "C-EUC1210"))
    )
    (comp (ref "C27")
      (value "4u7")
      (footprint "eagle-import:C1206")
      (libsource (lib "eagle-import") (part "C-EUC1206"))
    )
    (comp (ref "C28")
      (value "10n")
      (footprint "eagle-import:C0805")
      (libsource (lib "eagle-import") (part "C-EUC0805"))
    )
    (comp (ref "C29")
      (value "33p")
      (footprint "eagle-import:C0805")
      (libsource (lib "eagle-import") (part "C-EUC0805"))
    )
    (comp (ref "C30")
      (value "100n")
      (footprint "eagle-import:C0603")
      (libsource (lib "eagle-import") (part "C-EUC0603"))
    )
    (comp (ref "C31")
      (value "100n")
      (footprint "eagle-import:C0603")
      (libsource (lib "eagle-import") (part "C-EUC0603"))
    )
    (comp (ref "C32")
      (value "100n")
      (footprint "eagle-import:C0603")
      (libsource (lib "eagle-import") (part "C-EUC0603"))
    )
    (comp (ref "C33")
      (value "10n")
      (footprint "eagle-import:C0805")
      (libsource (lib "eagle-import") (part "C-EUC0805"))
    )
    (comp (ref "C34")
      (value "100n")
      (footprint "eagle-import:C0603")
      (libsource (lib "eagle-import") (part "C-EUC0603"))
    )
    (comp (ref "C35")
      (value "100n")
      (footprint "eagle-import:C0603")
      (libsource (lib "eagle-import") (part "C-EUC0603"))
    )
    (comp (ref "C36")
      (value "100n")
      (footprint "eagle-import:C0603")
      (libsource (lib "eagle-import") (part "C-EUC0603"))
    )
    (comp (ref "C37")
      (value "100n")
      (footprint "eagle-import:C0603")
      (libsource (lib "eagle-import") (part "C-EUC0603"))
    )
    (comp (ref "C38")
      (value "100n")
      (footprint "eagle-import:C0603")
      (libsource (lib "eagle-import") (part "C-EUC0603"))
    )
    (comp (ref "D4")
      (value "SKL16")
      (footprint "eagle-import:SOD123")
      (libsource (lib "eagle-import") (part "SCHOTTKYSOD123"))
    )
    (comp (ref "D5")
      (value "SKL16")
      (footprint "eagle-import:SOD123")
      (libsource (lib "eagle-import") (part "SCHOTTKYSOD123"))
    )
    (comp (ref "D6")
      (value "SKL14")
      (footprint "eagle-import:SOD123")
      (libsource (lib "eagle-import") (part "SCHOTTKYSOD123"))
    )
    (comp (ref "D7")
      (value "SKL14")
      (footprint "eagle-import:SOD123")
      (libsource (lib "eagle-import") (part "SCHOTTKYSOD123"))
    )
    (comp (ref "FB1")
      (value "60R@100MHz")
      (footprint "eagle-import:BEAD0603")
      (libsource (lib "eagle-import") (part "FERRITE_BEAD0603"))
    )
    (comp (ref "FB2")
      (value "60R@100MHz")
      (footprint "eagle-import:BEAD0603")
      (libsource (lib "eagle-import") (part "FERRITE_BEAD0603"))
    )
    (comp (ref "FB3")
      (value "60R@100MHz")
      (footprint "eagle-import:BEAD0603")
      (libsource (lib "eagle-import") (part "FERRITE_BEAD0603"))
    )
    (comp (ref "IC2")
      (value "TPS54060DGQ")
      (footprint "eagle-import:SOP50P490X110-11N")
      (fields (field (name "MPN") "TPS54060ADGQ"))
      (libsource (lib "eagle-import") (part "TPS54060DGQ"))
    )
    (comp (ref "IC3")
      (value "SI8641BB-B-IS1")
      (footprint "eagle-import:SOIC-16")
      (libsource (lib "eagle-import") (part "SI8641NSOIC-16"))
    )
    (comp (ref "IC4")
      (value "SN74LVC1G139DCUR")
      (footprint "eagle-import:DCU8")
      (libsource (lib "eagle-import") (part "SN74LVC1G139-VSSOP"))
    )
    (comp (ref "IC5")
      (value "MC78L05")
      (footprint "eagle-import:SOIC127P600X173-8N")
      (libsource (lib "eagle-import") (part "MC78LXXSOIC8"))
    )
    (comp (ref "IC6")
      (value "MC79L05")
      (footprint "eagle-import:SOIC127P600X173-8N")
      (libsource (lib "eagle-import") (part "MC79LXXSOIC"))
    )
    (comp (ref "IC7")
      (value "SI8641BB-B-IS1")
      (footprint "eagle-import:SOIC-16")
      (libsource (lib "eagle-import") (part "SI8641NSOIC-16"))
    )
    (comp (ref "IC8")
      (value "M24C32-WMN6P")
      (footprint "eagle-import:SOIC127P600X173-8N")
      (libsource (lib "eagle-import") (part "AT24CXXSOIC8"))
    )
    (comp (ref "KK1")
      (value "PMB-1")
      (footprint "eagle-import:PCB-MB")
      (libsource (lib "eagle-import") (part "PCB-MB"))
    )
    (comp (ref "KK2")
      (value "PMB-1")
      (footprint "eagle-import:PCB-MB")
      (libsource (lib "eagle-import") (part "PCB-MB"))
    )
    (comp (ref "R12")
      (value "10R")
      (footprint "eagle-import:R1206")
      (libsource (lib "eagle-import") (part "R-EU_R1206"))
    )
    (comp (ref "R13")
      (value "47K")
      (footprint "eagle-import:R0805")
      (libsource (lib "eagle-import") (part "R-EU_R0805"))
    )
    (comp (ref "R14")
      (value "10R")
      (footprint "eagle-import:R1206")
      (libsource (lib "eagle-import") (part "R-EU_R1206"))
    )
    (comp (ref "R15")
      (value "10R")
      (footprint "eagle-import:R1206")
      (libsource (lib "eagle-import") (part "R-EU_R1206"))
    )
    (comp (ref "R16")
      (value "2K2")
      (footprint "eagle-import:R0805")
      (libsource (lib "eagle-import") (part "R-EU_R0805"))
    )
    (comp (ref "R17")
      (value "10K")
      (footprint "eagle-import:R0805")
      (libsource (lib "eagle-import") (part "R-EU_R0805"))
    )
    (comp (ref "R18")
      (value "100K")
      (footprint "eagle-import:R0805")
      (libsource (lib "eagle-import") (part "R-EU_R0805"))
    )
    (comp (ref "R19")
      (value "330K")
      (footprint "eagle-import:R0805")
      (libsource (lib "eagle-import") (part "R-EU_R0805"))
    )
    (comp (ref "R20")
      (value "86K6")
      (footprint "eagle-import:R0805")
      (libsource (lib "eagle-import") (part "R-EU_R0805"))
    )
    (comp (ref "R21")
      (value "10K")
      (footprint "eagle-import:R0805")
      (libsource (lib "eagle-import") (part "R-EU_R0805"))
    )
    (comp (ref "R22")
      (value "10K")
      (footprint "eagle-import:R0805")
      (libsource (lib "eagle-import") (part "R-EU_R0805"))
    )
    (comp (ref "R23")
      (value "10K")
      (footprint "eagle-import:R0805")
      (libsource (lib "eagle-import") (part "R-EU_R0805"))
    )
    (comp (ref "R24")
      (value "10K")
      (footprint "eagle-import:R0805")
      (libsource (lib "eagle-import") (part "R-EU_R0805"))
    )
    (comp (ref "RN1")
      (value "DR1206-33R-4/8")
      (footprint "eagle-import:CAY16")
      (libsource (lib "eagle-import") (part "R_ARRAY4"))
    )
    (comp (ref "RN2")
      (value "DR1206-33R-4/8")
      (footprint "eagle-import:CAY16")
      (libsource (lib "eagle-import") (part "R_ARRAY4"))
    )
    (comp (ref "TR1")
      (value "SRF0703-821M")
      (footprint "eagle-import:SRF0703")
      (libsource (lib "eagle-import") (part "BOURNS_SRF0703INV"))
    )
    (comp (ref "X2")
      (value "77317-104-28LF")
      (footprint "eagle-import:77317-104-28LF")
      (libsource (lib "eagle-import") (part "77317-104-28LF"))
    )
  )
  (nets
    (net (code "1") (name "+3V3") (class "Default")
      (node (ref "C30") (pin "1") (pinfunction "1_1") (pintype "passive"))
      (node (ref "C35") (pin "1") (pinfunction "1_1") (pintype "passive"))
      (node (ref "C38") (pin "2") (pinfunction "2_2") (pintype "passive"))
      (node (ref "IC3") (pin "1") (pinfunction "VDD1_1") (pintype "passive"))
      (node (ref "IC3") (pin "7") (pinfunction "EN1_7") (pintype "input"))
      (node (ref "IC7") (pin "1") (pinfunction "VDD1_1") (pintype "passive"))
      (node (ref "IC7") (pin "7") (pinfunction "EN1_7") (pintype "input"))
      (node (ref "IC8") (pin "8") (pinfunction "VCC_8") (pintype "power_in"))
      (node (ref "R22") (pin "1") (pinfunction "1_1") (pintype "passive"))
      (node (ref "R23") (pin "1") (pinfunction "1_1") (pintype "passive"))
      (node (ref "R24") (pin "1") (pinfunction "1_1") (pintype "passive"))
      (node (ref "X2") (pin "1") (pinfunction "1_1") (pintype "passive"))
    )
    (net (code "2") (name "+5V") (class "Default")
      (node (ref "C31") (pin "2") (pinfunction "2_2") (pintype "passive"))
      (node (ref "C32") (pin "1") (pinfunction "1_1") (pintype "passive"))
      (node (ref "C36") (pin "2") (pinfunction "2_2") (pintype "passive"))
      (node (ref "C63") (pin "2") (pinfunction "2_2") (pintype "passive"))
      (node (ref "C64") (pin "2") (pinfunction "2_2") (pintype "passive"))
      (node (ref "C65") (pin "2") (pinfunction "2_2") (pintype "passive"))
      (node (ref "C66") (pin "1") (pinfunction "1_1") (pintype "passive"))
      (node (ref "C68") (pin "1") (pinfunction "1_1") (pintype "passive"))
      (node (ref "C79") (pin "2") (pinfunction "2_2") (pintype "passive"))
      (node (ref "C80") (pin "2") (pinfunction "2_2") (pintype "passive"))
      (node (ref "D20") (pin "C") (pinfunction "C_C") (pintype "passive"))
      (node (ref "FB2") (pin "P$2") (pinfunction "2_P$2") (pintype "passive"))
      (node (ref "IC12") (pin "7") (pinfunction "~{PRE}_7") (pintype "input"))
      (node (ref "IC12") (pin "8") (pinfunction "VDD_8") (pintype "power_in"))
      (node (ref "IC13") (pin "9") (pinfunction "VDD_9") (pintype "power_in"))
      (node (ref "IC15") (pin "5") (pinfunction "VDD_5") (pintype "passive"))
      (node (ref "IC18") (pin "13") (pinfunction "DVDD_13") (pintype "power_in"))
      (node (ref "IC3") (pin "10") (pinfunction "EN2_10") (pintype "input"))
      (node (ref "IC3") (pin "16") (pinfunction "VDD2_16") (pintype "passive"))
      (node (ref "IC4") (pin "8") (pinfunction "VCC_8") (pintype "passive"))
      (node (ref "IC7") (pin "10") (pinfunction "EN2_10") (pintype "input"))
      (node (ref "IC7") (pin "16") (pinfunction "VDD2_16") (pintype "passive"))
      (node (ref "K1") (pin "1") (pinfunction "+_1") (pintype "passive"))
      (node (ref "LED2") (pin "TA") (pinfunction "A_TA") (pintype "passive"))
      (node (ref "LED3") (pin "BA") (pinfunction "A_BA") (pintype "passive"))
      (node (ref "LED3") (pin "TA") (pinfunction "A_TA") (pintype "passive"))
      (node (ref "Q12") (pin "2") (pinfunction "S_2") (pintype "passive"))
      (node (ref "R107") (pin "2") (pinfunction "2_2") (pintype "passive"))
      (node (ref "R17") (pin "1") (pinfunction "1_1") (pintype "passive"))
      (node (ref "R69") (pin "1") (pinfunction "1_1") (pintype "passive"))
      (node (ref "R70") (pin "1") (pinfunction "1_1") (pintype "passive"))
      (node (ref "R71") (pin "1") (pinfunction "1_1") (pintype "passive"))
      (node (ref "R72") (pin "1") (pinfunction "1_1") (pintype "passive"))
      (node (ref "R84") (pin "2") (pinfunction "2_2") (pintype "passive"))
      (node (ref "R97") (pin "2") (pinfunction "2_2") (pintype "passive"))
    )
    (net (code "3") (name "+VNR") (class "Default")
      (node (ref "C27") (pin "1") (pinfunction "1_1") (pintype "passive"))
      (node (ref "IC5") (pin "8") (pinfunction "VI_8") (pintype "input"))
      (node (ref "R14") (pin "1") (pinfunction "1_1") (pintype "passive"))
    )
    (net (code "4") (name "+VREF") (class "Default")
      (node (ref "C69") (pin "+") (pinfunction "+_+") (pintype "passive"))
      (node (ref "C73") (pin "2") (pinfunction "2_2") (pintype "passive"))
      (node (ref "C83") (pin "2") (pinfunction "2_2") (pintype "passive"))
      (node (ref "IC14") (pin "6") (pinfunction "VOUT_6") (pintype "output"))
      (node (ref "IC16") (pin "2") (pinfunction "VREF_2") (pintype "input"))
      (node (ref "IC18") (pin "9") (pinfunction "REFP0_9") (pintype "input"))
      (node (ref "R31") (pin "1") (pinfunction "1_1") (pintype "passive"))
    )
    (net (code "5") (name "-9V") (class "Default")
      (node (ref "C21") (pin "1") (pinfunction "1_1") (pintype "passive"))
      (node (ref "IC6") (pin "2") (pinfunction "IN_2") (pintype "input"))
      (node (ref "IC6") (pin "3") (pinfunction "IN_3") (pintype "input"))
      (node (ref "IC6") (pin "6") (pinfunction "IN_6") (pintype "input"))
      (node (ref "IC6") (pin "7") (pinfunction "IN_7") (pintype "input"))
      (node (ref "R12") (pin "1") (pinfunction "1_1") (pintype "passive"))
      (node (ref "R28") (pin "1") (pinfunction "1_1") (pintype "passive"))
      (node (ref "R38") (pin "2") (pinfunction "2_2") (pintype "passive"))
      (node (ref "R39") (pin "2") (pinfunction "2_2") (pintype "passive"))
    )
    (net (code "6") (name "AUX_USET_SW") (class "Default")
      (node (ref "IC13") (pin "4") (pinfunction "GPB3_4") (pintype "bidirectional"))
      (node (ref "IC17") (pin "6") (pinfunction "CTRL_6") (pintype "input"))
      (node (ref "LED2") (pin "BA") (pinfunction "A_BA") (pintype "passive"))
    )
    (net (code "7") (name "CC_ACTIVE") (class "Default")
      (node (ref "IC13") (pin "22") (pinfunction "GPA1_22") (pintype "bidirectional"))
      (node (ref "Q16") (pin "1") (pinfunction "G_1") (pintype "passive"))
      (node (ref "R97") (pin "1") (pinfunction "1_1") (pintype "passive"))
      (node (ref "R99") (pin "2") (pinfunction "2_2") (pintype "passive"))
    )
    (net (code "8") (name "CSA") (class "Default")
      (node (ref "IC3") (pin "13") (pinfunction "B2_13") (pintype "output"))
      (node (ref "IC4") (pin "1") (pinfunction "A_1") (pintype "input"))
    )
    (net (code "9") (name "CSB") (class "Default")
      (node (ref "IC3") (pin "12") (pinfunction "B3_12") (pintype "output"))
      (node (ref "IC4") (pin "2") (pinfunction "B_2") (pintype "input"))
    )
    (net (code "10") (name "CS_ADC") (class "Default")
      (node (ref "IC18") (pin "2") (pinfunction "~{CS}_2") (pintype "input"))
      (node (ref "RN1") (pin "7") (pinfunction "2_7") (pintype "passive"))
    )
    (net (code "11") (name "CS_DAC") (class "Default")
      (node (ref "IC16") (pin "5") (pinfunction "~{SYNC}_5") (pintype "input"))
      (node (ref "RN1") (pin "8") (pinfunction "2_8") (pintype "passive"))
    )
    (net (code "12") (name "CS_IOEXP") (class "Default")
      (node (ref "IC13") (pin "11") (pinfunction "~{CS}_11") (pintype "input"))
      (node (ref "RN1") (pin "6") (pinfunction "2_6") (pintype "passive"))
    )
    (net (code "13") (name "CURR_5A") (class "Default")
      (node (ref "IC13") (pin "28") (pinfunction "GPA7_28") (pintype "bidirectional"))
      (node (ref "Q11") (pin "4") (pinfunction "G_4") (pintype "passive"))
      (node (ref "R65") (pin "2") (pinfunction "2_2") (pintype "passive"))
    )
    (net (code "14") (name "CURR_50MA") (class "Default")
      (node (ref "IC13") (pin "27") (pinfunction "GPA6_27") (pintype "bidirectional"))
      (node (ref "Q10") (pin "4") (pinfunction "G_4") (pintype "passive"))
      (node (ref "R60") (pin "2") (pinfunction "2_2") (pintype "passive"))
    )
    (net (code "15") (name "CV_ACTIVE") (class "Default")
      (node (ref "IC13") (pin "23") (pinfunction "GPA2_23") (pintype "bidirectional"))
      (node (ref "Q15") (pin "1") (pinfunction "G_1") (pintype "passive"))
      (node (ref "R84") (pin "1") (pinfunction "1_1") (pintype "passive"))
      (node (ref "R87") (pin "2") (pinfunction "2_2") (pintype "passive"))
    )
    (net (code "16") (name "DC+") (class "Default")
      (node (ref "C1") (pin "2") (pinfunction "2_2") (pintype "passive"))
      (node (ref "L1") (pin "1") (pinfunction "1_1") (pintype "passive"))
      (node (ref "R1") (pin "2") (pinfunction "2_2") (pintype "passive"))
      (node (ref "X1") (pin "1") (pinfunction "1_1") (pintype "passive"))
    )
    (net (code "17") (name "DC-") (class "Default")
      (node (ref "C1") (pin "1") (pinfunction "1_1") (pintype "passive"))
      (node (ref "L1") (pin "3") (pinfunction "1_3") (pintype "passive"))
      (node (ref "R1") (pin "1") (pinfunction "1_1") (pintype "passive"))
      (node (ref "X1") (pin "2") (pinfunction "1_2") (pintype "passive"))
    )
    (net (code "18") (name "DC_OUT") (class "Default")
      (node (ref "C2") (pin "+") (pinfunction "+_+") (pintype "passive"))
      (node (ref "C22") (pin "1") (pinfunction "1_1") (pintype "passive"))
      (node (ref "C23") (pin "1") (pinfunction "1_1") (pintype "passive"))
      (node (ref "C4") (pin "2") (pinfunction "2_2") (pintype "passive"))
      (node (ref "C5") (pin "1") (pinfunction "1_1") (pintype "passive"))
      (node (ref "C6") (pin "1") (pinfunction "1_1") (pintype "passive"))
      (node (ref "C7") (pin "1") (pinfunction "1_1") (pintype "passive"))
      (node (ref "C8") (pin "2") (pinfunction "2_2") (pintype "passive"))
      (node (ref "IC1") (pin "11") (pinfunction "VIN_11") (pintype "passive"))
      (node (ref "IC2") (pin "2") (pinfunction "VIN_2") (pintype "power_in"))
      (node (ref "L1") (pin "2") (pinfunction "2_2") (pintype "passive"))
      (node (ref "R13") (pin "2") (pinfunction "2_2") (pintype "passive"))
      (node (ref "R3") (pin "1") (pinfunction "1_1") (pintype "passive"))
      (node (ref "ZD1") (pin "C") (pinfunction "C_C") (pintype "passive"))
    )
    (net (code "19") (name "DIB_A0") (class "Default")
      (node (ref "IC8") (pin "1") (pinfunction "A0_1") (pintype "input"))
      (node (ref "R24") (pin "2") (pinfunction "2_2") (pintype "passive"))
      (node (ref "X2") (pin "17") (pinfunction "1_17") (pintype "passive"))
    )
    (net (code "20") (name "DIB_A1") (class "Default")
      (node (ref "IC8") (pin "2") (pinfunction "A1_2") (pintype "input"))
      (node (ref "R23") (pin "2") (pinfunction "2_2") (pintype "passive"))
      (node (ref "X2") (pin "19") (pinfunction "1_19") (pintype "passive"))
    )
    (net (code "21") (name "DIB_A2") (class "Default")
      (node (ref "IC8") (pin "3") (pinfunction "A2_3") (pintype "input"))
      (node (ref "R22") (pin "2") (pinfunction "2_2") (pintype "passive"))
      (node (ref "X2") (pin "18") (pinfunction "1_18") (pintype "passive"))
    )
    (net (code "22") (name "DIB_CSA") (class "Default")
      (node (ref "IC3") (pin "4") (pinfunction "A2_4") (pintype "input"))
      (node (ref "X2") (pin "9") (pinfunction "1_9") (pintype "passive"))
    )
    (net (code "23") (name "DIB_CSB") (class "Default")
      (node (ref "IC3") (pin "5") (pinfunction "A3_5") (pintype "input"))
      (node (ref "X2") (pin "12") (pinfunction "1_12") (pintype "passive"))
    )
    (net (code "24") (name "DIB_IRQ") (class "Default")
      (node (ref "IC7") (pin "6") (pinfunction "A4_6") (pintype "output"))
      (node (ref "X2") (pin "10") (pinfunction "1_10") (pintype "passive"))
    )
    (net (code "25") (name "DIB_MISO") (class "Default")
      (node (ref "IC3") (pin "6") (pinfunction "A4_6") (pintype "output"))
      (node (ref "X2") (pin "14") (pinfunction "1_14") (pintype "passive"))
    )
    (net (code "26") (name "DIB_MOSI") (class "Default")
      (node (ref "IC7") (pin "3") (pinfunction "A1_3") (pintype "input"))
      (node (ref "X2") (pin "15") (pinfunction "1_15") (pintype "passive"))
    )
    (net (code "27") (name "DIB_NRESET") (class "Default")
      (node (ref "IC7") (pin "5") (pinfunction "A3_5") (pintype "input"))
      (node (ref "X2") (pin "4") (pinfunction "1_4") (pintype "passive"))
    )
    (net (code "28") (name "DIB_SCL") (class "Default")
      (node (ref "IC8") (pin "6") (pinfunction "SCL_6") (pintype "bidirectional"))
      (node (ref "X2") (pin "5") (pinfunction "1_5") (pintype "passive"))
    )
    (net (code "29") (name "DIB_SCLK") (class "Default")
      (node (ref "IC3") (pin "3") (pinfunction "A1_3") (pintype "input"))
      (node (ref "X2") (pin "13") (pinfunction "1_13") (pintype "passive"))
    )
    (net (code "30") (name "DIB_SDA") (class "Default")
      (node (ref "IC8") (pin "5") (pinfunction "SDA_5") (pintype "bidirectional"))
      (node (ref "X2") (pin "8") (pinfunction "1_8") (pintype "passive"))
    )
    (net (code "31") (name "FB") (class "Default")
      (node (ref "C19") (pin "1") (pinfunction "1_1") (pintype "passive"))
      (node (ref "IC1") (pin "5") (pinfunction "VFB_5") (pintype "input"))
      (node (ref "Q2") (pin "C") (pinfunction "C_C") (pintype "passive"))
      (node (ref "R11") (pin "1") (pinfunction "1_1") (pintype "passive"))
      (node (ref "R9") (pin "2") (pinfunction "2_2") (pintype "passive"))
    )
    (net (code "32") (name "GCOM") (class "Default")
      (node (ref "IC10") (pin "6") (pinfunction "-IN_6") (pintype "input"))
      (node (ref "IC10") (pin "7") (pinfunction "OUT_7") (pintype "output"))
      (node (ref "R41") (pin "1") (pinfunction "1_1") (pintype "passive"))
      (node (ref "R58") (pin "1") (pinfunction "1_1") (pintype "passive"))
    )
    (net (code "33") (name "GND") (class "Default")
      (node (ref "C20") (pin "2") (pinfunction "2_2") (pintype "passive"))
      (node (ref "C21") (pin "2") (pinfunction "2_2") (pintype "passive"))
      (node (ref "C22") (pin "2") (pinfunction "2_2") (pintype "passive"))
      (node (ref "C23") (pin "2") (pinfunction "2_2") (pintype "passive"))
      (node (ref "C26") (pin "2") (pinfunction "2_2") (pintype "passive"))
      (node (ref "C27") (pin "2") (pinfunction "2_2") (pintype "passive"))
      (node (ref "C28") (pin "2") (pinfunction "2_2") (pintype "passive"))
      (node (ref "C29") (pin "1") (pinfunction "1_1") (pintype "passive"))
      (node (ref "C31") (pin "1") (pinfunction "1_1") (pintype "passive"))
      (node (ref "C32") (pin "2") (pinfunction "2_2") (pintype "passive"))
      (node (ref "C33") (pin "1") (pinfunction "1_1") (pintype "passive"))
      (node (ref "C34") (pin "2") (pinfunction "2_2") (pintype "passive"))
      (node (ref "C36") (pin "1") (pinfunction "1_1") (pintype "passive"))
      (node (ref "C37") (pin "1") (pinfunction "1_1") (pintype "passive"))
      (node (ref "C39") (pin "2") (pinfunction "2_2") (pintype "passive"))
      (node (ref "C42") (pin "2") (pinfunction "2_2") (pintype "passive"))
      (node (ref "C48") (pin "2") (pinfunction "2_2") (pintype "passive"))
      (node (ref "C49") (pin "1") (pinfunction "1_1") (pintype "passive"))
      (node (ref "C50") (pin "2") (pinfunction "2_2") (pintype "passive"))
      (node (ref "C51") (pin "1") (pinfunction "1_1") (pintype "passive"))
      (node (ref "C52") (pin "1") (pinfunction "1_1") (pintype "passive"))
      (node (ref "C53") (pin "1") (pinfunction "1_1") (pintype "passive"))
      (node (ref "C54") (pin "1") (pinfunction "1_1") (pintype "passive"))
      (node (ref "C56") (pin "1") (pinfunction "1_1") (pintype "passive"))
      (node (ref "C57") (pin "2") (pinfunction "2_2") (pintype "passive"))
      (node (ref "C58") (pin "1") (pinfunction "1_1") (pintype "passive"))
      (node (ref "C59") (pin "1") (pinfunction "1_1") (pintype "passive"))
      (node (ref "C65") (pin "1") (pinfunction "1_1") (pintype "passive"))
      (node (ref "C66") (pin "2") (pinfunction "2_2") (pintype "passive"))
      (node (ref "C67") (pin "2") (pinfunction "2_2") (pintype "passive"))
      (node (ref "C68") (pin "2") (pinfunction "2_2") (pintype "passive"))
      (node (ref "C69") (pin "-") (pinfunction "-_-") (pintype "passive"))
      (node (ref "C70") (pin "2") (pinfunction "2_2") (pintype "passive"))
      (node (ref "C71") (pin "2") (pinfunction "2_2") (pintype "passive"))
      (node (ref "C72") (pin "1") (pinfunction "1_1") (pintype "passive"))
      (node (ref "C73") (pin "1") (pinfunction "1_1") (pintype "passive"))
      (node (ref "C74") (pin "2") (pinfunction "2_2") (pintype "passive"))
      (node (ref "C75") (pin "1") (pinfunction "1_1") (pintype "passive"))
      (node (ref "C76") (pin "1") (pinfunction "1_1") (pintype "passive"))
      (node (ref "C77") (pin "2") (pinfunction "2_2") (pintype "passive"))
      (node (ref "C78") (pin "1") (pinfunction "1_1") (pintype "passive"))
      (node (ref "C79") (pin "1") (pinfunction "1_1") (pintype "passive"))
      (node (ref "C80") (pin "1") (pinfunction "1_1") (pintype "passive"))
      (node (ref "C81") (pin "1") (pinfunction "1_1") (pintype "passive"))
      (node (ref "C82") (pin "1") (pinfunction "1_1") (pintype "passive"))
      (node (ref "C83") (pin "1") (pinfunction "1_1") (pintype "passive"))
      (node (ref "C84") (pin "2") (pinfunction "2_2") (pintype "passive"))
      (node (ref "C85") (pin "1") (pinfunction "1_1") (pintype "passive"))
      (node (ref "C86") (pin "1") (pinfunction "1_1") (pintype "passive"))
      (node (ref "C88") (pin "1") (pinfunction "1_1") (pintype "passive"))
      (node (ref "C89") (pin "1") (pinfunction "1_1") (pintype "passive"))
      (node (ref "D10") (pin "C") (pinfunction "C_C") (pintype "passive"))
      (node (ref "D18") (pin "C") (pinfunction "C_C") (pintype "passive"))
      (node (ref "D5") (pin "A") (pinfunction "A_A") (pintype "passive"))
      (node (ref "D6") (pin "A") (pinfunction "A_A") (pintype "passive"))
      (node (ref "D7") (pin "C") (pinfunction "C_C") (pintype "passive"))
      (node (ref "D9") (pin "C") (pinfunction "C_C") (pintype "passive"))
      (node (ref "GND") (pin "1") (pinfunction "P$1_1") (pintype "bidirectional"))
      (node (ref "IC12") (pin "4") (pinfunction "VSS_4") (pintype "power_in"))
      (node (ref "IC13") (pin "10") (pinfunction "VSS_10") (pintype "power_in"))
      (node (ref "IC13") (pin "15") (pinfunction "A0_15") (pintype "input"))
      (node (ref "IC13") (pin "16") (pinfunction "A1_16") (pintype "input"))
      (node (ref "IC13") (pin "17") (pinfunction "A2_17") (pintype "input"))
      (node (ref "IC14") (pin "4") (pinfunction "GND_4") (pintype "passive"))
      (node (ref "IC15") (pin "2") (pinfunction "GND_2") (pintype "passive"))
      (node (ref "IC16") (pin "8") (pinfunction "GND_8") (pintype "power_in"))
      (node (ref "IC17") (pin "2") (pinfunction "GND_2") (pintype "passive"))
      (node (ref "IC18") (pin "3") (pinfunction "CLK_3") (pintype "bidirectional"))
      (node (ref "IC18") (pin "4") (pinfunction "DGND_4") (pintype "passive"))
      (node (ref "IC18") (pin "5") (pinfunction "AVSS_5") (pintype "passive"))
      (node (ref "IC18") (pin "8") (pinfunction "REFN0_8") (pintype "input"))
      (node (ref "IC2") (pin "9") (pinfunction "GND_9") (pintype "passive"))
      (node (ref "IC2") (pin "TP") (pinfunction "TP_TP") (pintype "passive"))
      (node (ref "IC20") (pin "4") (pinfunction "GND_4") (pintype "passive"))
      (node (ref "IC3") (pin "15") (pinfunction "GND2_15") (pintype "passive"))
      (node (ref "IC3") (pin "9") (pinfunction "GND2_2_9") (pintype "passive"))
      (node (ref "IC4") (pin "4") (pinfunction "GND_4") (pintype "passive"))
      (node (ref "IC5") (pin "2") (pinfunction "GND_2") (pintype "passive"))
      (node (ref "IC5") (pin "3") (pinfunction "GND_3") (pintype "passive"))
      (node (ref "IC5") (pin "6") (pinfunction "GND_6") (pintype "passive"))
      (node (ref "IC5") (pin "7") (pinfunction "GND_7") (pintype "passive"))
      (node (ref "IC6") (pin "5") (pinfunction "GND_5") (pintype "passive"))
      (node (ref "IC7") (pin "15") (pinfunction "GND2_15") (pintype "passive"))
      (node (ref "IC7") (pin "9") (pinfunction "GND2_2_9") (pintype "passive"))
      (node (ref "KK3") (pin "1") (pinfunction "1_1") (pintype "passive"))
      (node (ref "KK3") (pin "2") (pinfunction "2_2") (pintype "passive"))
      (node (ref "Q15") (pin "2") (pinfunction "S_2") (pintype "passive"))
      (node (ref "Q16") (pin "2") (pinfunction "S_2") (pintype "passive"))
      (node (ref "Q17") (pin "2") (pinfunction "S_2") (pintype "passive"))
      (node (ref "Q21") (pin "E") (pinfunction "E_E") (pintype "passive"))
      (node (ref "Q23") (pin "2") (pinfunction "S_2") (pintype "passive"))
      (node (ref "Q9") (pin "2") (pinfunction "S_2") (pintype "passive"))
      (node (ref "R111") (pin "1") (pinfunction "1_1") (pintype "passive"))
      (node (ref "R114") (pin "1") (pinfunction "1_1") (pintype "passive"))
      (node (ref "R15") (pin "1") (pinfunction "1_1") (pintype "passive"))
      (node (ref "R16") (pin "1") (pinfunction "1_1") (pintype "passive"))
      (node (ref "R19") (pin "1") (pinfunction "1_1") (pintype "passive"))
      (node (ref "R21") (pin "1") (pinfunction "1_1") (pintype "passive"))
      (node (ref "R37") (pin "2") (pinfunction "2_2") (pintype "passive"))
      (node (ref "R55") (pin "1") (pinfunction "1_1") (pintype "passive"))
      (node (ref "R60") (pin "1") (pinfunction "1_1") (pintype "passive"))
      (node (ref "R65") (pin "1") (pinfunction "1_1") (pintype "passive"))
      (node (ref "R73") (pin "2") (pinfunction "2_2") (pintype "passive"))
      (node (ref "R79") (pin "1") (pinfunction "1_1") (pintype "passive"))
      (node (ref "R88") (pin "2") (pinfunction "2_2") (pintype "passive"))
      (node (ref "R95") (pin "1") (pinfunction "1_1") (pintype "passive"))
      (node (ref "R96") (pin "1") (pinfunction "1_1") (pintype "passive"))
      (node (ref "SH1") (pin "2") (pinfunction "GND_B_2") (pintype "bidirectional"))
      (node (ref "TR1") (pin "4") (pinfunction "4_4") (pintype "passive"))
      (node (ref "X3") (pin "2") (pinfunction "1_2") (pintype "passive"))
      (node (ref "ZD3") (pin "1") (pinfunction "A_1") (pintype "passive"))
      (node (ref "ZD3") (pin "2") (pinfunction "A_2") (pintype "passive"))
    )
    (net (code "34") (name "GNDIO") (class "Default")
      (node (ref "C30") (pin "2") (pinfunction "2_2") (pintype "passive"))
      (node (ref "C35") (pin "2") (pinfunction "2_2") (pintype "passive"))
      (node (ref "C38") (pin "1") (pinfunction "1_1") (pintype "passive"))
      (node (ref "IC3") (pin "2") (pinfunction "GND1_2_2") (pintype "passive"))
      (node (ref "IC3") (pin "8") (pinfunction "GND1_8") (pintype "passive"))
      (node (ref "IC7") (pin "2") (pinfunction "GND1_2_2") (pintype "passive"))
      (node (ref "IC7") (pin "8") (pinfunction "GND1_8") (pintype "passive"))
      (node (ref "IC8") (pin "4") (pinfunction "GND_4") (pintype "passive"))
      (node (ref "IC8") (pin "7") (pinfunction "WP_7") (pintype "input"))
      (node (ref "X2") (pin "11") (pinfunction "1_11") (pintype "passive"))
      (node (ref "X2") (pin "16") (pinfunction "1_16") (pintype "passive"))
      (node (ref "X2") (pin "20") (pinfunction "1_20") (pintype "passive"))
      (node (ref "X2") (pin "25") (pinfunction "1_25") (pintype "passive"))
      (node (ref "X2") (pin "7") (pinfunction "1_7") (pintype "passive"))
    )
    (net (code "35") (name "IRQ") (class "Default")
      (node (ref "IC13") (pin "20") (pinfunction "INTA_20") (pintype "output"))
      (node (ref "IC7") (pin "11") (pinfunction "B4_11") (pintype "input"))
    )
    (net (code "36") (name "ISENSE+") (class "Default")
      (node (ref "IC11") (pin "3") (pinfunction "+IN_3") (pintype "input"))
      (node (ref "R58") (pin "2") (pinfunction "2_2") (pintype "passive"))
      (node (ref "R59") (pin "2") (pinfunction "2_2") (pintype "passive"))
    )
    (net (code "37") (name "ISENSE-") (class "Default")
      (node (ref "C62") (pin "1") (pinfunction "1_1") (pintype "passive"))
      (node (ref "IC11") (pin "2") (pinfunction "-IN_2") (pintype "input"))
      (node (ref "R64") (pin "1") (pinfunction "1_1") (pintype "passive"))
      (node (ref "R68") (pin "2") (pinfunction "2_2") (pintype "passive"))
    )
    (net (code "38") (name "I_MON") (class "Default")
      (node (ref "C62") (pin "2") (pinfunction "2_2") (pintype "passive"))
      (node (ref "IC11") (pin "6") (pinfunction "OUT_6") (pintype "output"))
      (node (ref "R62") (pin "1") (pinfunction "1_1") (pintype "passive"))
      (node (ref "R64") (pin "2") (pinfunction "2_2") (pintype "passive"))
      (node (ref "R81") (pin "1") (pinfunction "1_1") (pintype "passive"))
    )
    (net (code "39") (name "I_SERVO") (class "Default")
      (node (ref "C55") (pin "2") (pinfunction "2_2") (pintype "passive"))
      (node (ref "C60") (pin "2") (pinfunction "2_2") (pintype "passive"))
      (node (ref "D13") (pin "C") (pinfunction "C_C") (pintype "passive"))
      (node (ref "IC10") (pin "1") (pinfunction "OUT_1") (pintype "output"))
      (node (ref "R98") (pin "1") (pinfunction "1_1") (pintype "passive"))
    )
    (net (code "40") (name "I_SET") (class "Default")
      (node (ref "I_SET") (pin "2") (pinfunction "2_2") (pintype "passive"))
      (node (ref "R57") (pin "1") (pinfunction "1_1") (pintype "passive"))
      (node (ref "R77") (pin "1") (pinfunction "1_1") (pintype "passive"))
    )
    (net (code "41") (name "LOOP_CTRL") (class "Default")
      (node (ref "D12") (pin "A") (pinfunction "A_A") (pintype "passive"))
      (node (ref "D13") (pin "A") (pinfunction "A_A") (pintype "passive"))
      (node (ref "R40") (pin "1") (pinfunction "1_1") (pintype "passive"))
      (node (ref "R43") (pin "1") (pinfunction "1_1") (pintype "passive"))
      (node (ref "R93") (pin "2") (pinfunction "2_2") (pintype "passive"))
    )
    (net (code "42") (name "MISO") (class "Default")
      (node (ref "IC13") (pin "14") (pinfunction "SO_14") (pintype "output"))
      (node (ref "IC15") (pin "4") (pinfunction "SI/O_4") (pintype "bidirectional"))
      (node (ref "IC18") (pin "15") (pinfunction "DOUT/~{DRDY}_15") (pintype "output"))
      (node (ref "RN2") (pin "7") (pinfunction "2_7") (pintype "passive"))
    )
    (net (code "43") (name "MOSI") (class "Default")
      (node (ref "IC13") (pin "13") (pinfunction "SI_13") (pintype "input"))
      (node (ref "IC16") (pin "7") (pinfunction "DIN_7") (pintype "input"))
      (node (ref "IC18") (pin "16") (pinfunction "DIN_16") (pintype "input"))
      (node (ref "RN2") (pin "6") (pinfunction "2_6") (pintype "passive"))
    )
    (net (code "44") (name "Net-(C10-Pad1)") (class "Default")
      (node (ref "C10") (pin "1") (pinfunction "1_1") (pintype "passive"))
      (node (ref "C11") (pin "+") (pinfunction "+_+") (pintype "passive"))
      (node (ref "C15") (pin "1") (pinfunction "1_1") (pintype "passive"))
      (node (ref "C16") (pin "+") (pinfunction "+_+") (pintype "passive"))
      (node (ref "L2") (pin "2") (pinfunction "2_2") (pintype "passive"))
      (node (ref "L3") (pin "1") (pinfunction "1_1") (pintype "passive"))
      (node (ref "R4") (pin "1") (pinfunction "1_1") (pintype "passive"))
      (node (ref "R6") (pin "1") (pinfunction "1_1") (pintype "passive"))
      (node (ref "R7") (pin "1") (pinfunction "1_1") (pintype "passive"))
      (node (ref "R9") (pin "1") (pinfunction "1_1") (pintype "passive"))
    )
    (net (code "45") (name "Net-(C12-Pad2)") (class "Default")
      (node (ref "C12") (pin "2") (pinfunction "2_2") (pintype "passive"))
      (node (ref "R5") (pin "2") (pinfunction "2_2") (pintype "passive"))
    )
    (net (code "46") (name "Net-(C18-Pad1)") (class "Default")
      (node (ref "C18") (pin "1") (pinfunction "1_1") (pintype "passive"))
      (node (ref "R8") (pin "1") (pinfunction "1_1") (pintype "passive"))
    )
    (net (code "47") (name "Net-(C19-Pad2)") (class "Default")
      (node (ref "C19") (pin "2") (pinfunction "2_2") (pintype "passive"))
      (node (ref "D3") (pin "A") (pinfunction "A_A") (pintype "passive"))
      (node (ref "Q2") (pin "B") (pinfunction "B_B") (pintype "passive"))
      (node (ref "R10") (pin "1") (pinfunction "1_1") (pintype "passive"))
      (node (ref "R7") (pin "2") (pinfunction "2_2") (pintype "passive"))
    )
    (net (code "48") (name "Net-(C20-Pad1)") (class "Default")
      (node (ref "C20") (pin "1") (pinfunction "1_1") (pintype "passive"))
      (node (ref "D4") (pin "A") (pinfunction "A_A") (pintype "passive"))
      (node (ref "R12") (pin "2") (pinfunction "2_2") (pintype "passive"))
    )
    (net (code "49") (name "Net-(C25-Pad2)") (class "Default")
      (node (ref "C25") (pin "2") (pinfunction "2_2") (pintype "passive"))
      (node (ref "R15") (pin "2") (pinfunction "2_2") (pintype "passive"))
    )
    (net (code "50") (name "Net-(C26-Pad1)") (class "Default")
      (node (ref "C26") (pin "1") (pinfunction "1_1") (pintype "passive"))
      (node (ref "R14") (pin "2") (pinfunction "2_2") (pintype "passive"))
      (node (ref "R18") (pin "2") (pinfunction "2_2") (pintype "passive"))
      (node (ref "TR1") (pin "3") (pinfunction "3_3") (pintype "passive"))
    )
    (net (code "51") (name "Net-(C33-Pad2)") (class "Default")
      (node (ref "C33") (pin "2") (pinfunction "2_2") (pintype "passive"))
      (node (ref "R20") (pin "1") (pinfunction "1_1") (pintype "passive"))
    )
    (net (code "52") (name "Net-(C40-Pad1)") (class "Default")
      (node (ref "C40") (pin "1") (pinfunction "1_1") (pintype "passive"))
      (node (ref "D10") (pin "A") (pinfunction "A_A") (pintype "passive"))
      (node (ref "Q7") (pin "B") (pinfunction "B_B") (pintype "passive"))
      (node (ref "R42") (pin "2") (pinfunction "2_2") (pintype "passive"))
    )
    (net (code "53") (name "Net-(C40-Pad2)") (class "Default")
      (node (ref "C40") (pin "2") (pinfunction "2_2") (pintype "passive"))
      (node (ref "Q7") (pin "C") (pinfunction "C_C") (pintype "passive"))
      (node (ref "R36") (pin "2") (pinfunction "2_2") (pintype "passive"))
    )
    (net (code "54") (name "Net-(C41-Pad2)") (class "Default")
      (node (ref "C41") (pin "2") (pinfunction "2_2") (pintype "passive"))
      (node (ref "R44") (pin "1") (pinfunction "1_1") (pintype "passive"))
    )
    (net (code "55") (name "Net-(C42-Pad1)") (class "Default")
      (node (ref "C42") (pin "1") (pinfunction "1_1") (pintype "passive"))
      (node (ref "R47") (pin "1") (pinfunction "1_1") (pintype "passive"))
      (node (ref "R48") (pin "2") (pinfunction "2_2") (pintype "passive"))
    )
    (net (code "56") (name "Net-(C44-Pad1)") (class "Default")
      (node (ref "C44") (pin "1") (pinfunction "1_1") (pintype "passive"))
      (node (ref "R51") (pin "2") (pinfunction "2_2") (pintype "passive"))
    )
    (net (code "57") (name "Net-(C47-Pad2)") (class "Default")
      (node (ref "C47") (pin "2") (pinfunction "2_2") (pintype "passive"))
      (node (ref "R53") (pin "1") (pinfunction "1_1") (pintype "passive"))
    )
    (net (code "58") (name "Net-(C48-Pad1)") (class "Default")
      (node (ref "C48") (pin "1") (pinfunction "1_1") (pintype "passive"))
      (node (ref "R56") (pin "1") (pinfunction "1_1") (pintype "passive"))
      (node (ref "R57") (pin "2") (pinfunction "2_2") (pintype "passive"))
    )
    (net (code "59") (name "Net-(C55-Pad1)") (class "Default")
      (node (ref "C55") (pin "1") (pinfunction "1_1") (pintype "passive"))
      (node (ref "R63") (pin "1") (pinfunction "1_1") (pintype "passive"))
    )
    (net (code "60") (name "Net-(C61-Pad2)") (class "Default")
      (node (ref "C61") (pin "2") (pinfunction "2_2") (pintype "passive"))
      (node (ref "R66") (pin "1") (pinfunction "1_1") (pintype "passive"))
    )
    (net (code "61") (name "Net-(C90-Pad2)") (class "Default")
      (node (ref "C90") (pin "2") (pinfunction "2_2") (pintype "passive"))
      (node (ref "Q20") (pin "B") (pinfunction "B_B") (pintype "passive"))
      (node (ref "R103") (pin "1") (pinfunction "1_1") (pintype "passive"))
      (node (ref "R104") (pin "2") (pinfunction "2_2") (pintype "passive"))
      (node (ref "R106") (pin "2") (pinfunction "2_2") (pintype "passive"))
    )
    (net (code "62") (name "Net-(C91-Pad2)") (class "Default")
      (node (ref "C91") (pin "2") (pinfunction "2_2") (pintype "passive"))
      (node (ref "R109") (pin "2") (pinfunction "2_2") (pintype "passive"))
    )
    (net (code "63") (name "Net-(C98-Pad1)") (class "Default")
      (node (ref "C98") (pin "1") (pinfunction "1_1") (pintype "passive"))
      (node (ref "Q22") (pin "B") (pinfunction "B_B") (pintype "passive"))
      (node (ref "R110") (pin "1") (pinfunction "1_1") (pintype "passive"))
      (node (ref "R112") (pin "2") (pinfunction "2_2") (pintype "passive"))
    )
    (net (code "64") (name "Net-(D2-C)") (class "Default")
      (node (ref "C12") (pin "1") (pinfunction "1_1") (pintype "passive"))
      (node (ref "D2") (pin "3") (pinfunction "C_3") (pintype "passive"))
      (node (ref "L2") (pin "1") (pinfunction "1_1") (pintype "passive"))
      (node (ref "Q1") (pin "2") (pinfunction "D_2") (pintype "passive"))
    )
    (net (code "65") (name "Net-(D3-PadC)") (class "Default")
      (node (ref "D3") (pin "C") (pinfunction "C_C") (pintype "passive"))
      (node (ref "Q2") (pin "E") (pinfunction "E_E") (pintype "passive"))
      (node (ref "R6") (pin "2") (pinfunction "2_2") (pintype "passive"))
    )
    (net (code "66") (name "Net-(D4-PadC)") (class "Default")
      (node (ref "D4") (pin "C") (pinfunction "C_C") (pintype "passive"))
      (node (ref "TR1") (pin "2") (pinfunction "2_2") (pintype "passive"))
    )
    (net (code "67") (name "Net-(D17-PadA)") (class "Default")
      (node (ref "D17") (pin "A") (pinfunction "A_A") (pintype "passive"))
      (node (ref "Q14") (pin "B") (pinfunction "B_B") (pintype "passive"))
      (node (ref "R90") (pin "1") (pinfunction "1_1") (pintype "passive"))
      (node (ref "R95") (pin "2") (pinfunction "2_2") (pintype "passive"))
    )
    (net (code "68") (name "Net-(D17-PadC)") (class "Default")
      (node (ref "D17") (pin "C") (pinfunction "C_C") (pintype "passive"))
      (node (ref "D18") (pin "A") (pinfunction "A_A") (pintype "passive"))
    )
    (net (code "69") (name "Net-(FB1-1)") (class "Default")
      (node (ref "C34") (pin "1") (pinfunction "1_1") (pintype "passive"))
      (node (ref "D6") (pin "C") (pinfunction "C_C") (pintype "passive"))
      (node (ref "FB1") (pin "P$1") (pinfunction "1_P$1") (pintype "passive"))
      (node (ref "FB2") (pin "P$1") (pinfunction "1_P$1") (pintype "passive"))
      (node (ref "IC5") (pin "1") (pinfunction "VO_1") (pintype "passive"))
    )
    (net (code "70") (name "Net-(FB3-1)") (class "Default")
      (node (ref "C37") (pin "2") (pinfunction "2_2") (pintype "passive"))
      (node (ref "D7") (pin "A") (pinfunction "A_A") (pintype "passive"))
      (node (ref "FB3") (pin "P$1") (pinfunction "1_P$1") (pintype "passive"))
      (node (ref "IC6") (pin "1") (pinfunction "OUT_1") (pintype "passive"))
    )
    (net (code "71") (name "Net-(IC1-CAP)") (class "Default")
      (node (ref "C8") (pin "1") (pinfunction "1_1") (pintype "passive"))
      (node (ref "IC1") (pin "9") (pinfunction "CAP_9") (pintype "passive"))
    )
    (net (code "72") (name "Net-(IC1-GATE)") (class "Default")
      (node (ref "IC1") (pin "12") (pinfunction "GATE_12") (pintype "output"))
      (node (ref "Q1") (pin "1") (pinfunction "G_1") (pintype "passive"))
    )
    (net (code "73") (name "Net-(IC1-ITH)") (class "Default")
      (node (ref "C17") (pin "1") (pinfunction "1_1") (pintype "passive"))
      (node (ref "IC1") (pin "6") (pinfunction "ITH_6") (pintype "bidirectional"))
      (node (ref "R8") (pin "2") (pinfunction "2_2") (pintype "passive"))
    )
    (net (code "74") (name "Net-(IC1-RUN)") (class "Default")
      (node (ref "D1") (pin "C") (pinfunction "C_C") (pintype "passive"))
      (node (ref "IC1") (pin "8") (pinfunction "RUN_8") (pintype "input"))
      (node (ref "R2") (pin "2") (pinfunction "2_2") (pintype "passive"))
    )
    (net (code "75") (name "Net-(IC1-SENSE)") (class "Default")
      (node (ref "IC1") (pin "10") (pinfunction "SENSE_10") (pintype "input"))
      (node (ref "Q1") (pin "3") (pinfunction "S_3") (pintype "passive"))
      (node (ref "R3") (pin "2") (pinfunction "2_2") (pintype "passive"))
    )
    (net (code "76") (name "Net-(IC1-SS)") (class "Default")
      (node (ref "C9") (pin "2") (pinfunction "2_2") (pintype "passive"))
      (node (ref "IC1") (pin "4") (pinfunction "SS_4") (pintype "input"))
    )
    (net (code "77") (name "Net-(IC2-BOOT)") (class "Default")
      (node (ref "C24") (pin "2") (pinfunction "2_2") (pintype "passive"))
      (node (ref "IC2") (pin "1") (pinfunction "BOOT_1") (pintype "output"))
    )
    (net (code "78") (name "Net-(IC2-COMP)") (class "Default")
      (node (ref "C29") (pin "2") (pinfunction "2_2") (pintype "passive"))
      (node (ref "IC2") (pin "8") (pinfunction "COMP_8") (pintype "output"))
      (node (ref "R20") (pin "2") (pinfunction "2_2") (pintype "passive"))
    )
    (net (code "79") (name "Net-(IC2-EN)") (class "Default")
      (node (ref "IC2") (pin "3") (pinfunction "EN_3") (pintype "input"))
      (node (ref "R13") (pin "1") (pinfunction "1_1") (pintype "passive"))
      (node (ref "R16") (pin "2") (pinfunction "2_2") (pintype "passive"))
    )
    (net (code "80") (name "Net-(IC2-PH)") (class "Default")
      (node (ref "C24") (pin "1") (pinfunction "1_1") (pintype "passive"))
      (node (ref "C25") (pin "1") (pinfunction "1_1") (pintype "passive"))
      (node (ref "D5") (pin "C") (pinfunction "C_C") (pintype "passive"))
      (node (ref "IC2") (pin "10") (pinfunction "PH_10") (pintype "input"))
      (node (ref "TR1") (pin "1") (pinfunction "1_1") (pintype "passive"))
    )
    (net (code "81") (name "Net-(IC2-RT{slash}CLK)") (class "Default")
      (node (ref "IC2") (pin "5") (pinfunction "RT/CLK_5") (pintype "input"))
      (node (ref "R19") (pin "2") (pinfunction "2_2") (pintype "passive"))
    )
    (net (code "82") (name "Net-(IC2-SS{slash}TR)") (class "Default")
      (node (ref "C28") (pin "1") (pinfunction "1_1") (pintype "passive"))
      (node (ref "IC2") (pin "4") (pinfunction "SS/TR_4") (pintype "input"))
    )
    (net (code "83") (name "Net-(IC2-VSENSE)") (class "Default")
      (node (ref "IC2") (pin "7") (pinfunction "VSENSE_7") (pintype "input"))
      (node (ref "R18") (pin "1") (pinfunction "1_1") (pintype "passive"))
      (node (ref "R21") (pin "2") (pinfunction "2_2") (pintype "passive"))
    )
    (net (code "84") (name "Net-(IC3-B1)") (class "Default")
      (node (ref "IC3") (pin "14") (pinfunction "B1_14") (pintype "output"))
      (node (ref "RN2") (pin "1") (pinfunction "1_1") (pintype "passive"))
    )
    (net (code "85") (name "Net-(IC3-B4)") (class "Default")
      (node (ref "IC3") (pin "11") (pinfunction "B4_11") (pintype "input"))
      (node (ref "RN2") (pin "2") (pinfunction "1_2") (pintype "passive"))
    )
    (net (code "86") (name "Net-(IC4-Y0)") (class "Default")
      (node (ref "IC4") (pin "7") (pinfunction "Y0_7") (pintype "output"))
      (node (ref "RN1") (pin "1") (pinfunction "1_1") (pintype "passive"))
    )
    (net (code "87") (name "Net-(IC4-Y1)") (class "Default")
      (node (ref "IC4") (pin "6") (pinfunction "Y1_6") (pintype "output"))
      (node (ref "RN1") (pin "2") (pinfunction "1_2") (pintype "passive"))
    )
    (net (code "88") (name "Net-(IC4-Y2)") (class "Default")
      (node (ref "IC4") (pin "5") (pinfunction "Y2_5") (pintype "output"))
      (node (ref "RN1") (pin "3") (pinfunction "1_3") (pintype "passive"))
    )
    (net (code "89") (name "Net-(IC4-Y3)") (class "Default")
      (node (ref "IC4") (pin "3") (pinfunction "Y3_3") (pintype "output"))
      (node (ref "RN1") (pin "4") (pinfunction "1_4") (pintype "passive"))
    )
    (net (code "90") (name "Net-(IC7-B1)") (class "Default")
      (node (ref "IC7") (pin "14") (pinfunction "B1_14") (pintype "output"))
      (node (ref "RN2") (pin "3") (pinfunction "1_3") (pintype "passive"))
    )
    (net (code "91") (name "Net-(IC7-B2)") (class "Default")
      (node (ref "IC7") (pin "13") (pinfunction "B2_13") (pintype "output"))
      (node (ref "RN2") (pin "4") (pinfunction "1_4") (pintype "passive"))
    )
    (net (code "92") (name "Net-(IC9A-+IN)") (class "Default")
      (node (ref "IC9") (pin "3") (pinfunction "+IN_3") (pintype "input"))
      (node (ref "R44") (pin "2") (pinfunction "2_2") (pintype "passive"))
      (node (ref "R47") (pin "2") (pinfunction "2_2") (pintype "passive"))
    )
    (net (code "93") (name "Net-(IC9A--IN)") (class "Default")
      (node (ref "C46") (pin "1") (pinfunction "1_1") (pintype "passive"))
      (node (ref "IC9") (pin "2") (pinfunction "-IN_2") (pintype "input"))
      (node (ref "R51") (pin "1") (pinfunction "1_1") (pintype "passive"))
      (node (ref "R52") (pin "2") (pinfunction "2_2") (pintype "passive"))
      (node (ref "R53") (pin "2") (pinfunction "2_2") (pintype "passive"))
    )
    (net (code "94") (name "Net-(IC9B-+IN)") (class "Default")
      (node (ref "IC9") (pin "5") (pinfunction "+IN_5") (pintype "input"))
      (node (ref "R41") (pin "2") (pinfunction "2_2") (pintype "passive"))
      (node (ref "R45") (pin "1") (pinfunction "1_1") (pintype "passive"))
    )
    (net (code "95") (name "Net-(IC9B--IN)") (class "Default")
      (node (ref "C43") (pin "1") (pinfunction "1_1") (pintype "passive"))
      (node (ref "IC9") (pin "6") (pinfunction "-IN_6") (pintype "input"))
      (node (ref "R46") (pin "1") (pinfunction "1_1") (pintype "passive"))
      (node (ref "R50") (pin "2") (pinfunction "2_2") (pintype "passive"))
    )
    (net (code "96") (name "Net-(IC10A-+IN)") (class "Default")
      (node (ref "IC10") (pin "3") (pinfunction "+IN_3") (pintype "input"))
      (node (ref "R56") (pin "2") (pinfunction "2_2") (pintype "passive"))
    )
    (net (code "97") (name "Net-(IC10A--IN)") (class "Default")
      (node (ref "C60") (pin "1") (pinfunction "1_1") (pintype "passive"))
      (node (ref "IC10") (pin "2") (pinfunction "-IN_2") (pintype "input"))
      (node (ref "R62") (pin "2") (pinfunction "2_2") (pintype "passive"))
      (node (ref "R63") (pin "2") (pinfunction "2_2") (pintype "passive"))
      (node (ref "R66") (pin "2") (pinfunction "2_2") (pintype "passive"))
    )
    (net (code "98") (name "Net-(IC10B-+IN)") (class "Default")
      (node (ref "C39") (pin "1") (pinfunction "1_1") (pintype "passive"))
      (node (ref "IC10") (pin "5") (pinfunction "+IN_5") (pintype "input"))
      (node (ref "R31") (pin "2") (pinfunction "2_2") (pintype "passive"))
      (node (ref "R37") (pin "1") (pinfunction "1_1") (pintype "passive"))
    )
    (net (code "99") (name "Net-(IC12A-~{CLR})") (class "Default")
      (node (ref "D15") (pin "A") (pinfunction "A_A") (pintype "passive"))
      (node (ref "D16") (pin "A") (pinfunction "A_A") (pintype "passive"))
      (node (ref "IC12") (pin "6") (pinfunction "~{CLR}_6") (pintype "input"))
      (node (ref "R71") (pin "2") (pinfunction "2_2") (pintype "passive"))
    )
    (net (code "100") (name "Net-(IC13-~{RESET})") (class "Default")
      (node (ref "C63") (pin "1") (pinfunction "1_1") (pintype "passive"))
      (node (ref "IC13") (pin "18") (pinfunction "~{RESET}_18") (pintype "input"))
      (node (ref "JP1") (pin "2") (pinfunction "2_2") (pintype "passive"))
      (node (ref "R69") (pin "2") (pinfunction "2_2") (pintype "passive"))
    )
    (net (code "101") (name "Net-(IC14-TRIM{slash}NR)") (class "Default")
      (node (ref "C71") (pin "1") (pinfunction "1_1") (pintype "passive"))
      (node (ref "IC14") (pin "5") (pinfunction "TRIM/NR_5") (pintype "input"))
    )
    (net (code "102") (name "Net-(IC16-VOUTA)") (class "Default")
      (node (ref "IC16") (pin "4") (pinfunction "VOUTA_4") (pintype "output"))
      (node (ref "I_SET") (pin "1") (pinfunction "1_1") (pintype "passive"))
    )
    (net (code "103") (name "Net-(IC16-VOUTB)") (class "Default")
      (node (ref "IC16") (pin "3") (pinfunction "VOUTB_3") (pintype "output"))
      (node (ref "U_SET") (pin "1") (pinfunction "1_1") (pintype "passive"))
    )
    (net (code "104") (name "Net-(IC17-NO)") (class "Default")
      (node (ref "IC17") (pin "1") (pinfunction "NO_1") (pintype "bidirectional"))
      (node (ref "R75") (pin "1") (pinfunction "1_1") (pintype "passive"))
      (node (ref "ZD3") (pin "3") (pinfunction "C_3") (pintype "passive"))
    )
    (net (code "105") (name "Net-(IC18-AIN0{slash}REFP1)") (class "Default")
      (node (ref "C78") (pin "2") (pinfunction "2_2") (pintype "passive"))
      (node (ref "IC18") (pin "11") (pinfunction "AIN0/REFP1_11") (pintype "input"))
      (node (ref "R80") (pin "2") (pinfunction "2_2") (pintype "passive"))
    )
    (net (code "106") (name "Net-(IC18-AIN1)") (class "Default")
      (node (ref "C75") (pin "2") (pinfunction "2_2") (pintype "passive"))
      (node (ref "IC18") (pin "10") (pinfunction "AIN1_10") (pintype "input"))
      (node (ref "R77") (pin "2") (pinfunction "2_2") (pintype "passive"))
    )
    (net (code "107") (name "Net-(IC18-AIN2)") (class "Default")
      (node (ref "C76") (pin "2") (pinfunction "2_2") (pintype "passive"))
      (node (ref "IC18") (pin "7") (pinfunction "AIN2_7") (pintype "input"))
      (node (ref "R78") (pin "2") (pinfunction "2_2") (pintype "passive"))
    )
    (net (code "108") (name "Net-(IC18-AIN3{slash}REFN1)") (class "Default")
      (node (ref "C77") (pin "1") (pinfunction "1_1") (pintype "passive"))
      (node (ref "IC18") (pin "6") (pinfunction "AIN3/REFN1_6") (pintype "input"))
      (node (ref "R81") (pin "2") (pinfunction "2_2") (pintype "passive"))
    )
    (net (code "109") (name "Net-(IC18-AVDD)") (class "Default")
      (node (ref "C81") (pin "2") (pinfunction "2_2") (pintype "passive"))
      (node (ref "C82") (pin "2") (pinfunction "2_2") (pintype "passive"))
      (node (ref "IC18") (pin "12") (pinfunction "AVDD_12") (pintype "power_in"))
      (node (ref "R82") (pin "2") (pinfunction "2_2") (pintype "passive"))
    )
    (net (code "110") (name "Net-(IC19A-+IN)") (class "Default")
      (node (ref "IC19") (pin "3") (pinfunction "+IN_3") (pintype "input"))
      (node (ref "IC19") (pin "5") (pinfunction "+IN_5") (pintype "input"))
      (node (ref "R93") (pin "1") (pinfunction "1_1") (pintype "passive"))
    )
    (net (code "111") (name "Net-(IC19A--IN)") (class "Default")
      (node (ref "IC19") (pin "2") (pinfunction "-IN_2") (pintype "input"))
      (node (ref "R86") (pin "2") (pinfunction "2_2") (pintype "passive"))
    )
    (net (code "112") (name "Net-(IC19A-OUT)") (class "Default")
      (node (ref "IC19") (pin "1") (pinfunction "OUT_1") (pintype "output"))
      (node (ref "R87") (pin "1") (pinfunction "1_1") (pintype "passive"))
    )
    (net (code "113") (name "Net-(IC19B--IN)") (class "Default")
      (node (ref "IC19") (pin "6") (pinfunction "-IN_6") (pintype "input"))
      (node (ref "R98") (pin "2") (pinfunction "2_2") (pintype "passive"))
    )
    (net (code "114") (name "Net-(IC19B-OUT)") (class "Default")
      (node (ref "IC19") (pin "7") (pinfunction "OUT_7") (pintype "output"))
      (node (ref "R99") (pin "1") (pinfunction "1_1") (pintype "passive"))
    )
    (net (code "115") (name "Net-(IC20-+IN)") (class "Default")
      (node (ref "C86") (pin "2") (pinfunction "2_2") (pintype "passive"))
      (node (ref "C87") (pin "1") (pinfunction "1_1") (pintype "passive"))
      (node (ref "IC20") (pin "2") (pinfunction "+IN_2") (pintype "input"))
      (node (ref "R83") (pin "2") (pinfunction "2_2") (pintype "passive"))
      (node (ref "R88") (pin "1") (pinfunction "1_1") (pintype "passive"))
    )
    (net (code "116") (name "Net-(IC20--IN)") (class "Default")
      (node (ref "C87") (pin "2") (pinfunction "2_2") (pintype "passive"))
      (node (ref "IC20") (pin "3") (pinfunction "-IN_3") (pintype "input"))
      (node (ref "R94") (pin "2") (pinfunction "2_2") (pintype "passive"))
    )
    (net (code "117") (name "Net-(IC20-OUT)") (class "Default")
      (node (ref "IC20") (pin "7") (pinfunction "OUT_7") (pintype "output"))
      (node (ref "Q17") (pin "1") (pinfunction "G_1") (pintype "passive"))
      (node (ref "R100") (pin "2") (pinfunction "2_2") (pintype "passive"))
      (node (ref "R90") (pin "2") (pinfunction "2_2") (pintype "passive"))
    )
    (net (code "118") (name "Net-(K1A--)") (class "Default")
      (node (ref "D20") (pin "A") (pinfunction "A_A") (pintype "passive"))
      (node (ref "K1") (pin "8") (pinfunction "-_8") (pintype "passive"))
      (node (ref "Q23") (pin "3") (pinfunction "D_3") (pintype "passive"))
      (node (ref "R113") (pin "1") (pinfunction "1_1") (pintype "passive"))
    )
    (net (code "119") (name "Net-(K1B-S)") (class "Default")
      (node (ref "K1") (pin "4") (pinfunction "S_4") (pintype "passive"))
      (node (ref "X3") (pin "4") (pinfunction "1_4") (pintype "passive"))
    )
    (net (code "120") (name "Net-(K1C-S)") (class "Default")
      (node (ref "K1") (pin "5") (pinfunction "S_5") (pintype "passive"))
      (node (ref "X3") (pin "5") (pinfunction "1_5") (pintype "passive"))
    )
    (net (code "121") (name "Net-(LED1-C)") (class "Default")
      (node (ref "LED1") (pin "CC") (pinfunction "C_CC") (pintype "passive"))
      (node (ref "R73") (pin "1") (pinfunction "1_1") (pintype "passive"))
    )
    (net (code "122") (name "Net-(LED2A-C)") (class "Default")
      (node (ref "LED2") (pin "BC") (pinfunction "C_BC") (pintype "passive"))
      (node (ref "R79") (pin "2") (pinfunction "2_2") (pintype "passive"))
    )
    (net (code "123") (name "Net-(LED2B-C)") (class "Default")
      (node (ref "LED2") (pin "TC") (pinfunction "C_TC") (pintype "passive"))
      (node (ref "R113") (pin "2") (pinfunction "2_2") (pintype "passive"))
    )
    (net (code "124") (name "Net-(LED3A-C)") (class "Default")
      (node (ref "LED3") (pin "BC") (pinfunction "C_BC") (pintype "passive"))
      (node (ref "R91") (pin "2") (pinfunction "2_2") (pintype "passive"))
    )
    (net (code "125") (name "Net-(LED3B-C)") (class "Default")
      (node (ref "LED3") (pin "TC") (pinfunction "C_TC") (pintype "passive"))
      (node (ref "R89") (pin "1") (pinfunction "1_1") (pintype "passive"))
    )
    (net (code "126") (name "Net-(Q3-B)") (class "Default")
      (node (ref "Q3") (pin "1") (pinfunction "B_1") (pintype "passive"))
      (node (ref "R34") (pin "2") (pinfunction "2_2") (pintype "passive"))
    )
    (net (code "127") (name "Net-(Q3-E)") (class "Default")
      (node (ref "Q3") (pin "3") (pinfunction "E_3") (pintype "passive"))
      (node (ref "R25") (pin "2") (pinfunction "2_2") (pintype "passive"))
    )
    (net (code "128") (name "Net-(Q4-B)") (class "Default")
      (node (ref "Q4") (pin "1") (pinfunction "B_1") (pintype "passive"))
      (node (ref "R35") (pin "2") (pinfunction "2_2") (pintype "passive"))
    )
    (net (code "129") (name "Net-(Q4-E)") (class "Default")
      (node (ref "Q4") (pin "3") (pinfunction "E_3") (pintype "passive"))
      (node (ref "R26") (pin "2") (pinfunction "2_2") (pintype "passive"))
    )
    (net (code "130") (name "Net-(Q5-G)") (class "Default")
      (node (ref "Q5") (pin "1") (pinfunction "G_1") (pintype "passive"))
      (node (ref "Q6") (pin "2") (pinfunction "C_2") (pintype "passive"))
      (node (ref "Q6") (pin "4") (pinfunction "C_4") (pintype "passive"))
      (node (ref "R30") (pin "2") (pinfunction "2_2") (pintype "passive"))
      (node (ref "ZD2") (pin "A") (pinfunction "A_A") (pintype "passive"))
    )
    (net (code "131") (name "Net-(Q5-S)") (class "Default")
      (node (ref "Q5") (pin "3") (pinfunction "S_3") (pintype "passive"))
      (node (ref "R29") (pin "1") (pinfunction "1_1") (pintype "passive"))
    )
    (net (code "132") (name "Net-(Q6-B)") (class "Default")
      (node (ref "Q6") (pin "1") (pinfunction "B_1") (pintype "passive"))
      (node (ref "R36") (pin "1") (pinfunction "1_1") (pintype "passive"))
      (node (ref "R38") (pin "1") (pinfunction "1_1") (pintype "passive"))
    )
    (net (code "133") (name "Net-(Q6-E)") (class "Default")
      (node (ref "Q6") (pin "3") (pinfunction "E_3") (pintype "passive"))
      (node (ref "R39") (pin "1") (pinfunction "1_1") (pintype "passive"))
    )
    (net (code "134") (name "Net-(Q8-B)") (class "Default")
      (node (ref "D11") (pin "C") (pinfunction "C_C") (pintype "passive"))
      (node (ref "Q8") (pin "1") (pinfunction "B_1") (pintype "passive"))
      (node (ref "R43") (pin "2") (pinfunction "2_2") (pintype "passive"))
    )
    (net (code "135") (name "Net-(Q8-C-Pad2)") (class "Default")
      (node (ref "Q8") (pin "2") (pinfunction "C_2") (pintype "passive"))
      (node (ref "Q8") (pin "4") (pinfunction "C_4") (pintype "passive"))
      (node (ref "R33") (pin "1") (pinfunction "1_1") (pintype "passive"))
      (node (ref "R34") (pin "1") (pinfunction "1_1") (pintype "passive"))
      (node (ref "R35") (pin "1") (pinfunction "1_1") (pintype "passive"))
    )
    (net (code "136") (name "Net-(Q8-E)") (class "Default")
      (node (ref "D11") (pin "A") (pinfunction "A_A") (pintype "passive"))
      (node (ref "Q8") (pin "3") (pinfunction "E_3") (pintype "passive"))
      (node (ref "R49") (pin "2") (pinfunction "2_2") (pintype "passive"))
    )
    (net (code "137") (name "Net-(Q9-D)") (class "Default")
      (node (ref "C45") (pin "2") (pinfunction "2_2") (pintype "passive"))
      (node (ref "Q9") (pin "3") (pinfunction "D_3") (pintype "passive"))
      (node (ref "R49") (pin "1") (pinfunction "1_1") (pintype "passive"))
    )
    (net (code "138") (name "Net-(Q9-G)") (class "Default")
      (node (ref "C45") (pin "1") (pinfunction "1_1") (pintype "passive"))
      (node (ref "Q9") (pin "1") (pinfunction "G_1") (pintype "passive"))
      (node (ref "R54") (pin "1") (pinfunction "1_1") (pintype "passive"))
      (node (ref "R55") (pin "2") (pinfunction "2_2") (pintype "passive"))
    )
    (net (code "139") (name "Net-(Q10-S-Pad1)") (class "Default")
      (node (ref "Q10") (pin "1") (pinfunction "S_1") (pintype "passive"))
      (node (ref "Q10") (pin "2") (pinfunction "S_2") (pintype "passive"))
      (node (ref "Q10") (pin "3") (pinfunction "S_3") (pintype "passive"))
      (node (ref "R59") (pin "1") (pinfunction "1_1") (pintype "passive"))
      (node (ref "R61") (pin "1") (pinfunction "1_1") (pintype "passive"))
    )
    (net (code "140") (name "Net-(Q11-S-Pad1)") (class "Default")
      (node (ref "Q11") (pin "1") (pinfunction "S_1") (pintype "passive"))
      (node (ref "Q11") (pin "2") (pinfunction "S_2") (pintype "passive"))
      (node (ref "Q11") (pin "3") (pinfunction "S_3") (pintype "passive"))
      (node (ref "R67") (pin "2") (pinfunction "2_2") (pintype "passive"))
    )
    (net (code "141") (name "Net-(Q12-D)") (class "Default")
      (node (ref "Q12") (pin "3") (pinfunction "D_3") (pintype "passive"))
      (node (ref "R74") (pin "2") (pinfunction "2_2") (pintype "passive"))
    )
    (net (code "142") (name "Net-(Q13-PadA2)") (class "Default")
      (node (ref "Q13") (pin "A2") (pinfunction "A2_A2") (pintype "passive"))
      (node (ref "R92") (pin "2") (pinfunction "2_2") (pintype "passive"))
    )
    (net (code "143") (name "Net-(Q13-PadG)") (class "Default")
      (node (ref "Q13") (pin "G") (pinfunction "G_G") (pintype "passive"))
      (node (ref "Q14") (pin "C") (pinfunction "C_C") (pintype "passive"))
      (node (ref "R85") (pin "1") (pinfunction "1_1") (pintype "passive"))
    )
    (net (code "144") (name "Net-(Q14-PadE)") (class "Default")
      (node (ref "Q14") (pin "E") (pinfunction "E_E") (pintype "passive"))
      (node (ref "R96") (pin "2") (pinfunction "2_2") (pintype "passive"))
    )
    (net (code "145") (name "Net-(Q15-D)") (class "Default")
      (node (ref "Q15") (pin "3") (pinfunction "D_3") (pintype "passive"))
      (node (ref "R89") (pin "2") (pinfunction "2_2") (pintype "passive"))
    )
    (net (code "146") (name "Net-(Q16-D)") (class "Default")
      (node (ref "Q16") (pin "3") (pinfunction "D_3") (pintype "passive"))
      (node (ref "R91") (pin "1") (pinfunction "1_1") (pintype "passive"))
    )
    (net (code "147") (name "Net-(Q18-G)") (class "Default")
      (node (ref "Q18") (pin "4") (pinfunction "G_4") (pintype "passive"))
      (node (ref "Q19") (pin "C") (pinfunction "C_C") (pintype "passive"))
      (node (ref "R100") (pin "1") (pinfunction "1_1") (pintype "passive"))
    )
    (net (code "148") (name "Net-(Q19-PadB)") (class "Default")
      (node (ref "Q19") (pin "B") (pinfunction "B_B") (pintype "passive"))
      (node (ref "R101") (pin "1") (pinfunction "1_1") (pintype "passive"))
      (node (ref "R102") (pin "2") (pinfunction "2_2") (pintype "passive"))
    )
    (net (code "149") (name "Net-(Q20-PadC)") (class "Default")
      (node (ref "Q20") (pin "C") (pinfunction "C_C") (pintype "passive"))
      (node (ref "R108") (pin "2") (pinfunction "2_2") (pintype "passive"))
    )
    (net (code "150") (name "Net-(Q21-PadB)") (class "Default")
      (node (ref "Q21") (pin "B") (pinfunction "B_B") (pintype "passive"))
      (node (ref "R108") (pin "1") (pinfunction "1_1") (pintype "passive"))
      (node (ref "R111") (pin "2") (pinfunction "2_2") (pintype "passive"))
    )
    (net (code "151") (name "Net-(Q22-PadC)") (class "Default")
      (node (ref "Q22") (pin "C") (pinfunction "C_C") (pintype "passive"))
      (node (ref "R105") (pin "1") (pinfunction "1_1") (pintype "passive"))
    )
    (net (code "152") (name "Net-(R27-Pad1)") (class "Default")
      (node (ref "R27") (pin "1") (pinfunction "1_1") (pintype "passive"))
      (node (ref "R32") (pin "2") (pinfunction "2_2") (pintype "passive"))
    )
    (net (code "153") (name "Net-(R61-Pad2)") (class "Default")
      (node (ref "R61") (pin "2") (pinfunction "2_2") (pintype "passive"))
      (node (ref "R67") (pin "2S") (pinfunction "2S_2S") (pintype "passive"))
    )
    (net (code "154") (name "Net-(R67-Pad1S)") (class "Default")
      (node (ref "R67") (pin "1S") (pinfunction "1S_1S") (pintype "passive"))
      (node (ref "R68") (pin "1") (pinfunction "1_1") (pintype "passive"))
    )
    (net (code "155") (name "Net-(R75-Pad2)") (class "Default")
      (node (ref "R75") (pin "2") (pinfunction "2_2") (pintype "passive"))
      (node (ref "R76") (pin "1") (pinfunction "1_1") (pintype "passive"))
    )
    (net (code "156") (name "Net-(R76-Pad2)") (class "Default")
      (node (ref "R76") (pin "2") (pinfunction "2_2") (pintype "passive"))
      (node (ref "X3") (pin "1") (pinfunction "1_1") (pintype "passive"))
    )
    (net (code "157") (name "Net-(R101-Pad2)") (class "Default")
      (node (ref "R101") (pin "2") (pinfunction "2_2") (pintype "passive"))
      (node (ref "ZD4") (pin "A") (pinfunction "A_A") (pintype "passive"))
    )
    (net (code "158") (name "Net-(R105-Pad2)") (class "Default")
      (node (ref "R105") (pin "2") (pinfunction "2_2") (pintype "passive"))
      (node (ref "R106") (pin "1") (pinfunction "1_1") (pintype "passive"))
    )
    (net (code "159") (name "Net-(X4B-1)") (class "Default")
      (node (ref "F2") (pin "2") (pinfunction "2_2") (pintype "passive"))
      (node (ref "X4") (pin "10") (pinfunction "1_10") (pintype "passive"))
      (node (ref "X4") (pin "6") (pinfunction "1_6") (pintype "passive"))
      (node (ref "X4") (pin "7") (pinfunction "1_7") (pintype "passive"))
      (node (ref "X4") (pin "8") (pinfunction "1_8") (pintype "passive"))
      (node (ref "X4") (pin "9") (pinfunction "1_9") (pintype "passive"))
    )
    (net (code "160") (name "OE") (class "Default")
      (node (ref "IC13") (pin "2") (pinfunction "GPB1_2") (pintype "bidirectional"))
      (node (ref "OE") (pin "1") (pinfunction "1_1") (pintype "passive"))
    )
    (net (code "161") (name "OE_GREEN") (class "Default")
      (node (ref "IC13") (pin "7") (pinfunction "GPB6_7") (pintype "bidirectional"))
      (node (ref "LED1") (pin "GREEN") (pinfunction "AG_GREEN") (pintype "passive"))
    )
    (net (code "162") (name "OE_RED") (class "Default")
      (node (ref "IC13") (pin "8") (pinfunction "GPB7_8") (pintype "bidirectional"))
      (node (ref "LED1") (pin "RED") (pinfunction "AR_RED") (pintype "passive"))
    )
    (net (code "163") (name "OE_SYNC") (class "Default")
      (node (ref "IC7") (pin "4") (pinfunction "A2_4") (pintype "input"))
      (node (ref "X2") (pin "6") (pinfunction "1_6") (pintype "passive"))
    )
    (net (code "164") (name "OE_TRIG") (class "Default")
      (node (ref "IC12") (pin "1") (pinfunction "CLK_1") (pintype "input"))
      (node (ref "RN2") (pin "5") (pinfunction "2_5") (pintype "passive"))
    )
    (net (code "165") (name "OUTC+") (class "Default")
      (node (ref "C93") (pin "1") (pinfunction "1_1") (pintype "passive"))
      (node (ref "C94") (pin "+") (pinfunction "+_+") (pintype "passive"))
      (node (ref "C95") (pin "1") (pinfunction "1_1") (pintype "passive"))
      (node (ref "C96") (pin "1") (pinfunction "1_1") (pintype "passive"))
      (node (ref "J2") (pin "1") (pinfunction "1_1") (pintype "passive"))
      (node (ref "J2") (pin "NC1") (pinfunction "1_NC1") (pintype "passive"))
      (node (ref "J2") (pin "NC2") (pinfunction "1_NC2") (pintype "passive"))
      (node (ref "J2") (pin "NC3") (pinfunction "1_NC3") (pintype "passive"))
      (node (ref "J2") (pin "NC4") (pinfunction "1_NC4") (pintype "passive"))
      (node (ref "X4") (pin "1") (pinfunction "1_1") (pintype "passive"))
      (node (ref "X4") (pin "2") (pinfunction "1_2") (pintype "passive"))
      (node (ref "X4") (pin "3") (pinfunction "1_3") (pintype "passive"))
      (node (ref "X4") (pin "4") (pinfunction "1_4") (pintype "passive"))
      (node (ref "X4") (pin "5") (pinfunction "1_5") (pintype "passive"))
    )
    (net (code "166") (name "OUTC-") (class "Default")
      (node (ref "C94") (pin "-") (pinfunction "-_-") (pintype "passive"))
      (node (ref "C95") (pin "2") (pinfunction "2_2") (pintype "passive"))
      (node (ref "C96") (pin "2") (pinfunction "2_2") (pintype "passive"))
      (node (ref "C97") (pin "2") (pinfunction "2_2") (pintype "passive"))
      (node (ref "J3") (pin "1") (pinfunction "1_1") (pintype "passive"))
      (node (ref "J3") (pin "NC1") (pinfunction "1_NC1") (pintype "passive"))
      (node (ref "J3") (pin "NC2") (pinfunction "1_NC2") (pintype "passive"))
      (node (ref "J3") (pin "NC3") (pinfunction "1_NC3") (pintype "passive"))
      (node (ref "J3") (pin "NC4") (pinfunction "1_NC4") (pintype "passive"))
      (node (ref "X4") (pin "16") (pinfunction "1_16") (pintype "passive"))
      (node (ref "X4") (pin "17") (pinfunction "1_17") (pintype "passive"))
      (node (ref "X4") (pin "18") (pinfunction "1_18") (pintype "passive"))
      (node (ref "X4") (pin "19") (pinfunction "1_19") (pintype "passive"))
      (node (ref "X4") (pin "20") (pinfunction "1_20") (pintype "passive"))
    )
    (net (code "167") (name "OVP_EN") (class "Default")
      (node (ref "IC13") (pin "5") (pinfunction "GPB4_5") (pintype "bidirectional"))
      (node (ref "IC20") (pin "6") (pinfunction "~{SHDN}_6") (pintype "input"))
    )
    (net (code "168") (name "PE") (class "Default")
      (node (ref "C3") (pin "2") (pinfunction "2_2") (pintype "passive"))
      (node (ref "C4") (pin "1") (pinfunction "1_1") (pintype "passive"))
      (node (ref "C93") (pin "2") (pinfunction "2_2") (pintype "passive"))
      (node (ref "C97") (pin "1") (pinfunction "1_1") (pintype "passive"))
      (node (ref "J1") (pin "1") (pinfunction "P$1_1") (pintype "bidirectional"))
      (node (ref "J1") (pin "2") (pinfunction "P$1_2") (pintype "bidirectional"))
      (node (ref "X3") (pin "3") (pinfunction "1_3") (pintype "passive"))
    )
    (net (code "169") (name "POST_OE") (class "Default")
      (node (ref "IC12") (pin "5") (pinfunction "Q_5") (pintype "output"))
      (node (ref "R54") (pin "2") (pinfunction "2_2") (pintype "passive"))
    )
    (net (code "170") (name "POST_OUT+") (class "Default")
      (node (ref "C47") (pin "1") (pinfunction "1_1") (pintype "passive"))
      (node (ref "C61") (pin "1") (pinfunction "1_1") (pintype "passive"))
      (node (ref "D8") (pin "A") (pinfunction "A_A") (pintype "passive"))
      (node (ref "F1") (pin "1") (pinfunction "1_1") (pintype "passive"))
      (node (ref "Q3") (pin "2") (pinfunction "C_2") (pintype "passive"))
      (node (ref "Q4") (pin "2") (pinfunction "C_2") (pintype "passive"))
      (node (ref "R10") (pin "2") (pinfunction "2_2") (pintype "passive"))
      (node (ref "R27") (pin "2") (pinfunction "2_2") (pintype "passive"))
      (node (ref "R28") (pin "2") (pinfunction "2_2") (pintype "passive"))
      (node (ref "R29") (pin "2") (pinfunction "2_2") (pintype "passive"))
      (node (ref "R30") (pin "1") (pinfunction "1_1") (pintype "passive"))
      (node (ref "ZD2") (pin "C") (pinfunction "C_C") (pintype "passive"))
    )
    (net (code "171") (name "POST_OUT-") (class "Default")
      (node (ref "C41") (pin "1") (pinfunction "1_1") (pintype "passive"))
      (node (ref "C92") (pin "-") (pinfunction "-_-") (pintype "passive"))
      (node (ref "C98") (pin "2") (pinfunction "2_2") (pintype "passive"))
      (node (ref "D14") (pin "A") (pinfunction "A_A") (pintype "passive"))
      (node (ref "D19") (pin "1") (pinfunction "A_1") (pintype "passive"))
      (node (ref "D19") (pin "2") (pinfunction "A_2") (pintype "passive"))
      (node (ref "JP4") (pin "1") (pinfunction "1_1") (pintype "passive"))
      (node (ref "K1") (pin "7") (pinfunction "O_7") (pintype "passive"))
      (node (ref "Q10") (pin "MB") (pinfunction "D_MB") (pintype "passive"))
      (node (ref "Q11") (pin "MB") (pinfunction "D_MB") (pintype "passive"))
      (node (ref "Q22") (pin "E") (pinfunction "E_E") (pintype "passive"))
      (node (ref "R109") (pin "1") (pinfunction "1_1") (pintype "passive"))
      (node (ref "R112") (pin "1") (pinfunction "1_1") (pintype "passive"))
      (node (ref "X4") (pin "11") (pinfunction "1_11") (pintype "passive"))
      (node (ref "X4") (pin "12") (pinfunction "1_12") (pintype "passive"))
      (node (ref "X4") (pin "13") (pinfunction "1_13") (pintype "passive"))
      (node (ref "X4") (pin "14") (pinfunction "1_14") (pintype "passive"))
      (node (ref "X4") (pin "15") (pinfunction "1_15") (pintype "passive"))
    )
    (net (code "172") (name "POST_OUTF+") (class "Default")
      (node (ref "C90") (pin "1") (pinfunction "1_1") (pintype "passive"))
      (node (ref "C91") (pin "1") (pinfunction "1_1") (pintype "passive"))
      (node (ref "C92") (pin "+") (pinfunction "+_+") (pintype "passive"))
      (node (ref "D19") (pin "3") (pinfunction "C_3") (pintype "passive"))
      (node (ref "F1") (pin "2") (pinfunction "2_2") (pintype "passive"))
      (node (ref "F2") (pin "1") (pinfunction "1_1") (pintype "passive"))
      (node (ref "JP3") (pin "2") (pinfunction "2_2") (pintype "passive"))
      (node (ref "K1") (pin "2") (pinfunction "O_2") (pintype "passive"))
      (node (ref "Q13") (pin "A1") (pinfunction "A1_A1") (pintype "passive"))
      (node (ref "Q18") (pin "MB") (pinfunction "D_MB") (pintype "passive"))
      (node (ref "Q20") (pin "E") (pinfunction "E_E") (pintype "passive"))
      (node (ref "R103") (pin "2") (pinfunction "2_2") (pintype "passive"))
      (node (ref "R85") (pin "2") (pinfunction "2_2") (pintype "passive"))
      (node (ref "ZD4") (pin "C") (pinfunction "C_C") (pintype "passive"))
    )
    (net (code "173") (name "PREG_IN-") (class "Default")
      (node (ref "C10") (pin "2") (pinfunction "2_2") (pintype "passive"))
      (node (ref "C11") (pin "-") (pinfunction "-_-") (pintype "passive"))
      (node (ref "C15") (pin "2") (pinfunction "2_2") (pintype "passive"))
      (node (ref "C16") (pin "-") (pinfunction "-_-") (pintype "passive"))
      (node (ref "C2") (pin "-") (pinfunction "-_-") (pintype "passive"))
      (node (ref "C3") (pin "1") (pinfunction "1_1") (pintype "passive"))
      (node (ref "C5") (pin "2") (pinfunction "2_2") (pintype "passive"))
      (node (ref "C6") (pin "2") (pinfunction "2_2") (pintype "passive"))
      (node (ref "C7") (pin "2") (pinfunction "2_2") (pintype "passive"))
      (node (ref "D2") (pin "1") (pinfunction "A_1") (pintype "passive"))
      (node (ref "D2") (pin "2") (pinfunction "A_2") (pintype "passive"))
      (node (ref "IC1") (pin "TP") (pinfunction "PGND_TP") (pintype "passive"))
      (node (ref "L1") (pin "4") (pinfunction "2_4") (pintype "passive"))
      (node (ref "R2") (pin "1") (pinfunction "1_1") (pintype "passive"))
      (node (ref "R5") (pin "1") (pinfunction "1_1") (pintype "passive"))
      (node (ref "SH1") (pin "1") (pinfunction "GND_A_1") (pintype "bidirectional"))
      (node (ref "SH2") (pin "2") (pinfunction "GND_B_2") (pintype "bidirectional"))
      (node (ref "SH3") (pin "2") (pinfunction "GND_B_2") (pintype "bidirectional"))
      (node (ref "ZD1") (pin "A") (pinfunction "A_A") (pintype "passive"))
    )
    (net (code "174") (name "PREG_OUT+") (class "Default")
      (node (ref "C13") (pin "+") (pinfunction "+_+") (pintype "passive"))
      (node (ref "C14") (pin "1") (pinfunction "1_1") (pintype "passive"))
      (node (ref "D8") (pin "C") (pinfunction "C_C") (pintype "passive"))
      (node (ref "L3") (pin "2") (pinfunction "2_2") (pintype "passive"))
      (node (ref "R25") (pin "1") (pinfunction "1_1") (pintype "passive"))
      (node (ref "R26") (pin "1") (pinfunction "1_1") (pintype "passive"))
      (node (ref "R33") (pin "2") (pinfunction "2_2") (pintype "passive"))
      (node (ref "R4") (pin "2") (pinfunction "2_2") (pintype "passive"))
    )
    (net (code "175") (name "PREG_OUT-") (class "Default")
      (node (ref "C13") (pin "-") (pinfunction "-_-") (pintype "passive"))
      (node (ref "C14") (pin "2") (pinfunction "2_2") (pintype "passive"))
      (node (ref "D14") (pin "C") (pinfunction "C_C") (pintype "passive"))
      (node (ref "Q18") (pin "1") (pinfunction "S_1") (pintype "passive"))
      (node (ref "Q18") (pin "2") (pinfunction "S_2") (pintype "passive"))
      (node (ref "Q18") (pin "3") (pinfunction "S_3") (pintype "passive"))
      (node (ref "Q19") (pin "E") (pinfunction "E_E") (pintype "passive"))
      (node (ref "Q5") (pin "2") (pinfunction "D_2") (pintype "passive"))
      (node (ref "R102") (pin "1") (pinfunction "1_1") (pintype "passive"))
      (node (ref "R32") (pin "1") (pinfunction "1_1") (pintype "passive"))
      (node (ref "R67") (pin "1") (pinfunction "1_1") (pintype "passive"))
      (node (ref "R92") (pin "1") (pinfunction "1_1") (pintype "passive"))
      (node (ref "SH2") (pin "1") (pinfunction "GND_A_1") (pintype "bidirectional"))
    )
    (net (code "176") (name "PRE_OE") (class "Default")
      (node (ref "D1") (pin "A") (pinfunction "A_A") (pintype "passive"))
      (node (ref "IC12") (pin "2") (pinfunction "D_2") (pintype "input"))
      (node (ref "OE") (pin "2") (pinfunction "2_2") (pintype "passive"))
    )
    (net (code "177") (name "PWRGOOD") (class "Default")
      (node (ref "D16") (pin "C") (pinfunction "C_C") (pintype "passive"))
      (node (ref "IC13") (pin "24") (pinfunction "GPA3_24") (pintype "bidirectional"))
      (node (ref "IC2") (pin "6") (pinfunction "PWRGD_6") (pintype "output"))
      (node (ref "R17") (pin "2") (pinfunction "2_2") (pintype "passive"))
    )
    (net (code "178") (name "RSENSE") (class "Default")
      (node (ref "IC13") (pin "3") (pinfunction "GPB2_3") (pintype "bidirectional"))
      (node (ref "Q23") (pin "1") (pinfunction "G_1") (pintype "passive"))
      (node (ref "R114") (pin "2") (pinfunction "2_2") (pintype "passive"))
    )
    (net (code "179") (name "SCLK") (class "Default")
      (node (ref "IC13") (pin "12") (pinfunction "SCK_12") (pintype "input"))
      (node (ref "IC15") (pin "3") (pinfunction "SCLK_3") (pintype "input"))
      (node (ref "IC16") (pin "6") (pinfunction "SCLK_6") (pintype "input"))
      (node (ref "IC18") (pin "1") (pinfunction "SCLK_1") (pintype "input"))
      (node (ref "RN2") (pin "8") (pinfunction "2_8") (pintype "passive"))
    )
    (net (code "180") (name "SENSE+") (class "Default")
      (node (ref "JP3") (pin "1") (pinfunction "1_1") (pintype "passive"))
      (node (ref "K1") (pin "3") (pinfunction "P_3") (pintype "passive"))
      (node (ref "R104") (pin "1") (pinfunction "1_1") (pintype "passive"))
      (node (ref "R45") (pin "2") (pinfunction "2_2") (pintype "passive"))
    )
    (net (code "181") (name "SENSE-") (class "Default")
      (node (ref "JP4") (pin "2") (pinfunction "2_2") (pintype "passive"))
      (node (ref "K1") (pin "6") (pinfunction "P_6") (pintype "passive"))
      (node (ref "R110") (pin "2") (pinfunction "2_2") (pintype "passive"))
      (node (ref "R46") (pin "2") (pinfunction "2_2") (pintype "passive"))
    )
    (net (code "182") (name "SENSE_ERR") (class "Default")
      (node (ref "IC13") (pin "21") (pinfunction "GPA0_21") (pintype "bidirectional"))
      (node (ref "Q21") (pin "C") (pinfunction "C_C") (pintype "passive"))
      (node (ref "R107") (pin "1") (pinfunction "1_1") (pintype "passive"))
    )
    (net (code "183") (name "SGND") (class "Default")
      (node (ref "C17") (pin "2") (pinfunction "2_2") (pintype "passive"))
      (node (ref "C18") (pin "2") (pinfunction "2_2") (pintype "passive"))
      (node (ref "C9") (pin "1") (pinfunction "1_1") (pintype "passive"))
      (node (ref "IC1") (pin "1") (pinfunction "PLLIN/MODE_1") (pintype "input"))
      (node (ref "IC1") (pin "2") (pinfunction "FREQ_2") (pintype "input"))
      (node (ref "IC1") (pin "3") (pinfunction "SGND_3") (pintype "passive"))
      (node (ref "R11") (pin "2") (pinfunction "2_2") (pintype "passive"))
      (node (ref "SH3") (pin "1") (pinfunction "GND_A_1") (pintype "bidirectional"))
    )
    (net (code "184") (name "TEMP_CS") (class "Default")
      (node (ref "IC15") (pin "1") (pinfunction "~{CS}_1") (pintype "input"))
      (node (ref "RN1") (pin "5") (pinfunction "2_5") (pintype "passive"))
    )
    (net (code "185") (name "U_MON") (class "Default")
      (node (ref "C43") (pin "2") (pinfunction "2_2") (pintype "passive"))
      (node (ref "IC9") (pin "7") (pinfunction "OUT_7") (pintype "output"))
      (node (ref "R50") (pin "1") (pinfunction "1_1") (pintype "passive"))
      (node (ref "R52") (pin "1") (pinfunction "1_1") (pintype "passive"))
      (node (ref "R80") (pin "1") (pinfunction "1_1") (pintype "passive"))
      (node (ref "R83") (pin "1") (pinfunction "1_1") (pintype "passive"))
    )
    (net (code "186") (name "U_SERVO") (class "Default")
      (node (ref "C44") (pin "2") (pinfunction "2_2") (pintype "passive"))
      (node (ref "C46") (pin "2") (pinfunction "2_2") (pintype "passive"))
      (node (ref "D12") (pin "C") (pinfunction "C_C") (pintype "passive"))
      (node (ref "IC9") (pin "1") (pinfunction "OUT_1") (pintype "output"))
      (node (ref "R42") (pin "1") (pinfunction "1_1") (pintype "passive"))
      (node (ref "R86") (pin "1") (pinfunction "1_1") (pintype "passive"))
    )
    (net (code "187") (name "U_SET") (class "Default")
      (node (ref "IC17") (pin "3") (pinfunction "NC_3") (pintype "bidirectional"))
      (node (ref "JP2") (pin "1") (pinfunction "1_1") (pintype "passive"))
      (node (ref "R78") (pin "1") (pinfunction "1_1") (pintype "passive"))
      (node (ref "U_SET") (pin "2") (pinfunction "2_2") (pintype "passive"))
    )
    (net (code "188") (name "U_SET_OUT") (class "Default")
      (node (ref "IC17") (pin "4") (pinfunction "COM_4") (pintype "bidirectional"))
      (node (ref "JP2") (pin "2") (pinfunction "2_2") (pintype "passive"))
      (node (ref "R48") (pin "1") (pinfunction "1_1") (pintype "passive"))
      (node (ref "R94") (pin "1") (pinfunction "1_1") (pintype "passive"))
    )
    (net (code "189") (name "V+") (class "Default")
      (node (ref "C49") (pin "2") (pinfunction "2_2") (pintype "passive"))
      (node (ref "C50") (pin "1") (pinfunction "1_1") (pintype "passive"))
      (node (ref "C51") (pin "2") (pinfunction "2_2") (pintype "passive"))
      (node (ref "C52") (pin "2") (pinfunction "2_2") (pintype "passive"))
      (node (ref "C53") (pin "2") (pinfunction "2_2") (pintype "passive"))
      (node (ref "C67") (pin "1") (pinfunction "1_1") (pintype "passive"))
      (node (ref "C70") (pin "1") (pinfunction "1_1") (pintype "passive"))
      (node (ref "C72") (pin "2") (pinfunction "2_2") (pintype "passive"))
      (node (ref "C74") (pin "1") (pinfunction "1_1") (pintype "passive"))
      (node (ref "C84") (pin "1") (pinfunction "1_1") (pintype "passive"))
      (node (ref "C85") (pin "2") (pinfunction "2_2") (pintype "passive"))
      (node (ref "C88") (pin "2") (pinfunction "2_2") (pintype "passive"))
      (node (ref "FB1") (pin "P$2") (pinfunction "2_P$2") (pintype "passive"))
      (node (ref "IC10") (pin "8") (pinfunction "V+_8") (pintype "power_in"))
      (node (ref "IC11") (pin "7") (pinfunction "V+_7") (pintype "power_in"))
      (node (ref "IC14") (pin "2") (pinfunction "VIN_2") (pintype "passive"))
      (node (ref "IC16") (pin "1") (pinfunction "VDD_1") (pintype "power_in"))
      (node (ref "IC17") (pin "5") (pinfunction "VDD_5") (pintype "power_in"))
      (node (ref "IC19") (pin "8") (pinfunction "V+_8") (pintype "power_in"))
      (node (ref "IC20") (pin "1") (pinfunction "+VCC_1") (pintype "passive"))
      (node (ref "IC20") (pin "5") (pinfunction "~{LE}_5") (pintype "input"))
      (node (ref "IC9") (pin "8") (pinfunction "V+_8") (pintype "power_in"))
      (node (ref "R40") (pin "2") (pinfunction "2_2") (pintype "passive"))
      (node (ref "R82") (pin "1") (pinfunction "1_1") (pintype "passive"))
    )
    (net (code "190") (name "V-") (class "Default")
      (node (ref "C54") (pin "2") (pinfunction "2_2") (pintype "passive"))
      (node (ref "C56") (pin "2") (pinfunction "2_2") (pintype "passive"))
      (node (ref "C57") (pin "1") (pinfunction "1_1") (pintype "passive"))
      (node (ref "C58") (pin "2") (pinfunction "2_2") (pintype "passive"))
      (node (ref "C59") (pin "2") (pinfunction "2_2") (pintype "passive"))
      (node (ref "C89") (pin "2") (pinfunction "2_2") (pintype "passive"))
      (node (ref "FB3") (pin "P$2") (pinfunction "2_P$2") (pintype "passive"))
      (node (ref "IC10") (pin "4") (pinfunction "V-_4") (pintype "power_in"))
      (node (ref "IC11") (pin "4") (pinfunction "V-_4") (pintype "power_in"))
      (node (ref "IC19") (pin "4") (pinfunction "V-_4") (pintype "power_in"))
      (node (ref "IC9") (pin "4") (pinfunction "V-_4") (pintype "power_in"))
    )
    (net (code "191") (name "unconnected-(IC1-PGOOD-Pad7)") (class "Default")
      (node (ref "IC1") (pin "7") (pinfunction "PGOOD_7") (pintype "output"))
    )
    (net (code "192") (name "unconnected-(IC12A-~{Q}-Pad3)") (class "Default")
      (node (ref "IC12") (pin "3") (pinfunction "~{Q}_3") (pintype "output"))
    )
    (net (code "193") (name "unconnected-(IC13-GPB5-Pad6)") (class "Default")
      (node (ref "IC13") (pin "6") (pinfunction "GPB5_6") (pintype "bidirectional"))
    )
    (net (code "194") (name "unconnected-(IC13-INTB-Pad19)") (class "Default")
      (node (ref "IC13") (pin "19") (pinfunction "INTB_19") (pintype "output"))
    )
    (net (code "195") (name "unconnected-(IC14-TEMP-Pad3)") (class "Default")
      (node (ref "IC14") (pin "3") (pinfunction "TEMP_3") (pintype "input"))
    )
    (net (code "196") (name "~{ADC_DRDY}") (class "Default")
      (node (ref "IC13") (pin "25") (pinfunction "GPA4_25") (pintype "bidirectional"))
      (node (ref "IC18") (pin "14") (pinfunction "~{DRDY}_14") (pintype "output"))
    )
    (net (code "197") (name "~{DP_DRIVE}") (class "Default")
      (node (ref "D9") (pin "A") (pinfunction "A_A") (pintype "passive"))
      (node (ref "Q7") (pin "E") (pinfunction "E_E") (pintype "passive"))
      (node (ref "R74") (pin "1") (pinfunction "1_1") (pintype "passive"))
    )
    (net (code "198") (name "~{OVP_FAULT}") (class "Default")
      (node (ref "C64") (pin "1") (pinfunction "1_1") (pintype "passive"))
      (node (ref "D15") (pin "C") (pinfunction "C_C") (pintype "passive"))
      (node (ref "IC13") (pin "26") (pinfunction "GPA5_26") (pintype "bidirectional"))
      (node (ref "Q17") (pin "3") (pinfunction "D_3") (pintype "passive"))
      (node (ref "R70") (pin "2") (pinfunction "2_2") (pintype "passive"))
    )
    (net (code "199") (name "~{RESET}") (class "Default")
      (node (ref "IC7") (pin "12") (pinfunction "B3_12") (pintype "output"))
      (node (ref "JP1") (pin "1") (pinfunction "1_1") (pintype "passive"))
    )
    (net (code "200") (name "~{SET_DP}") (class "Default")
      (node (ref "IC13") (pin "1") (pinfunction "GPB0_1") (pintype "bidirectional"))
      (node (ref "Q12") (pin "1") (pinfunction "G_1") (pintype "passive"))
      (node (ref "R72") (pin "2") (pinfunction "2_2") (pintype "passive"))
    )
  )
)
